# milliLearn-ice40.net
KiCad netlist of a schematic drawn in EAGLE
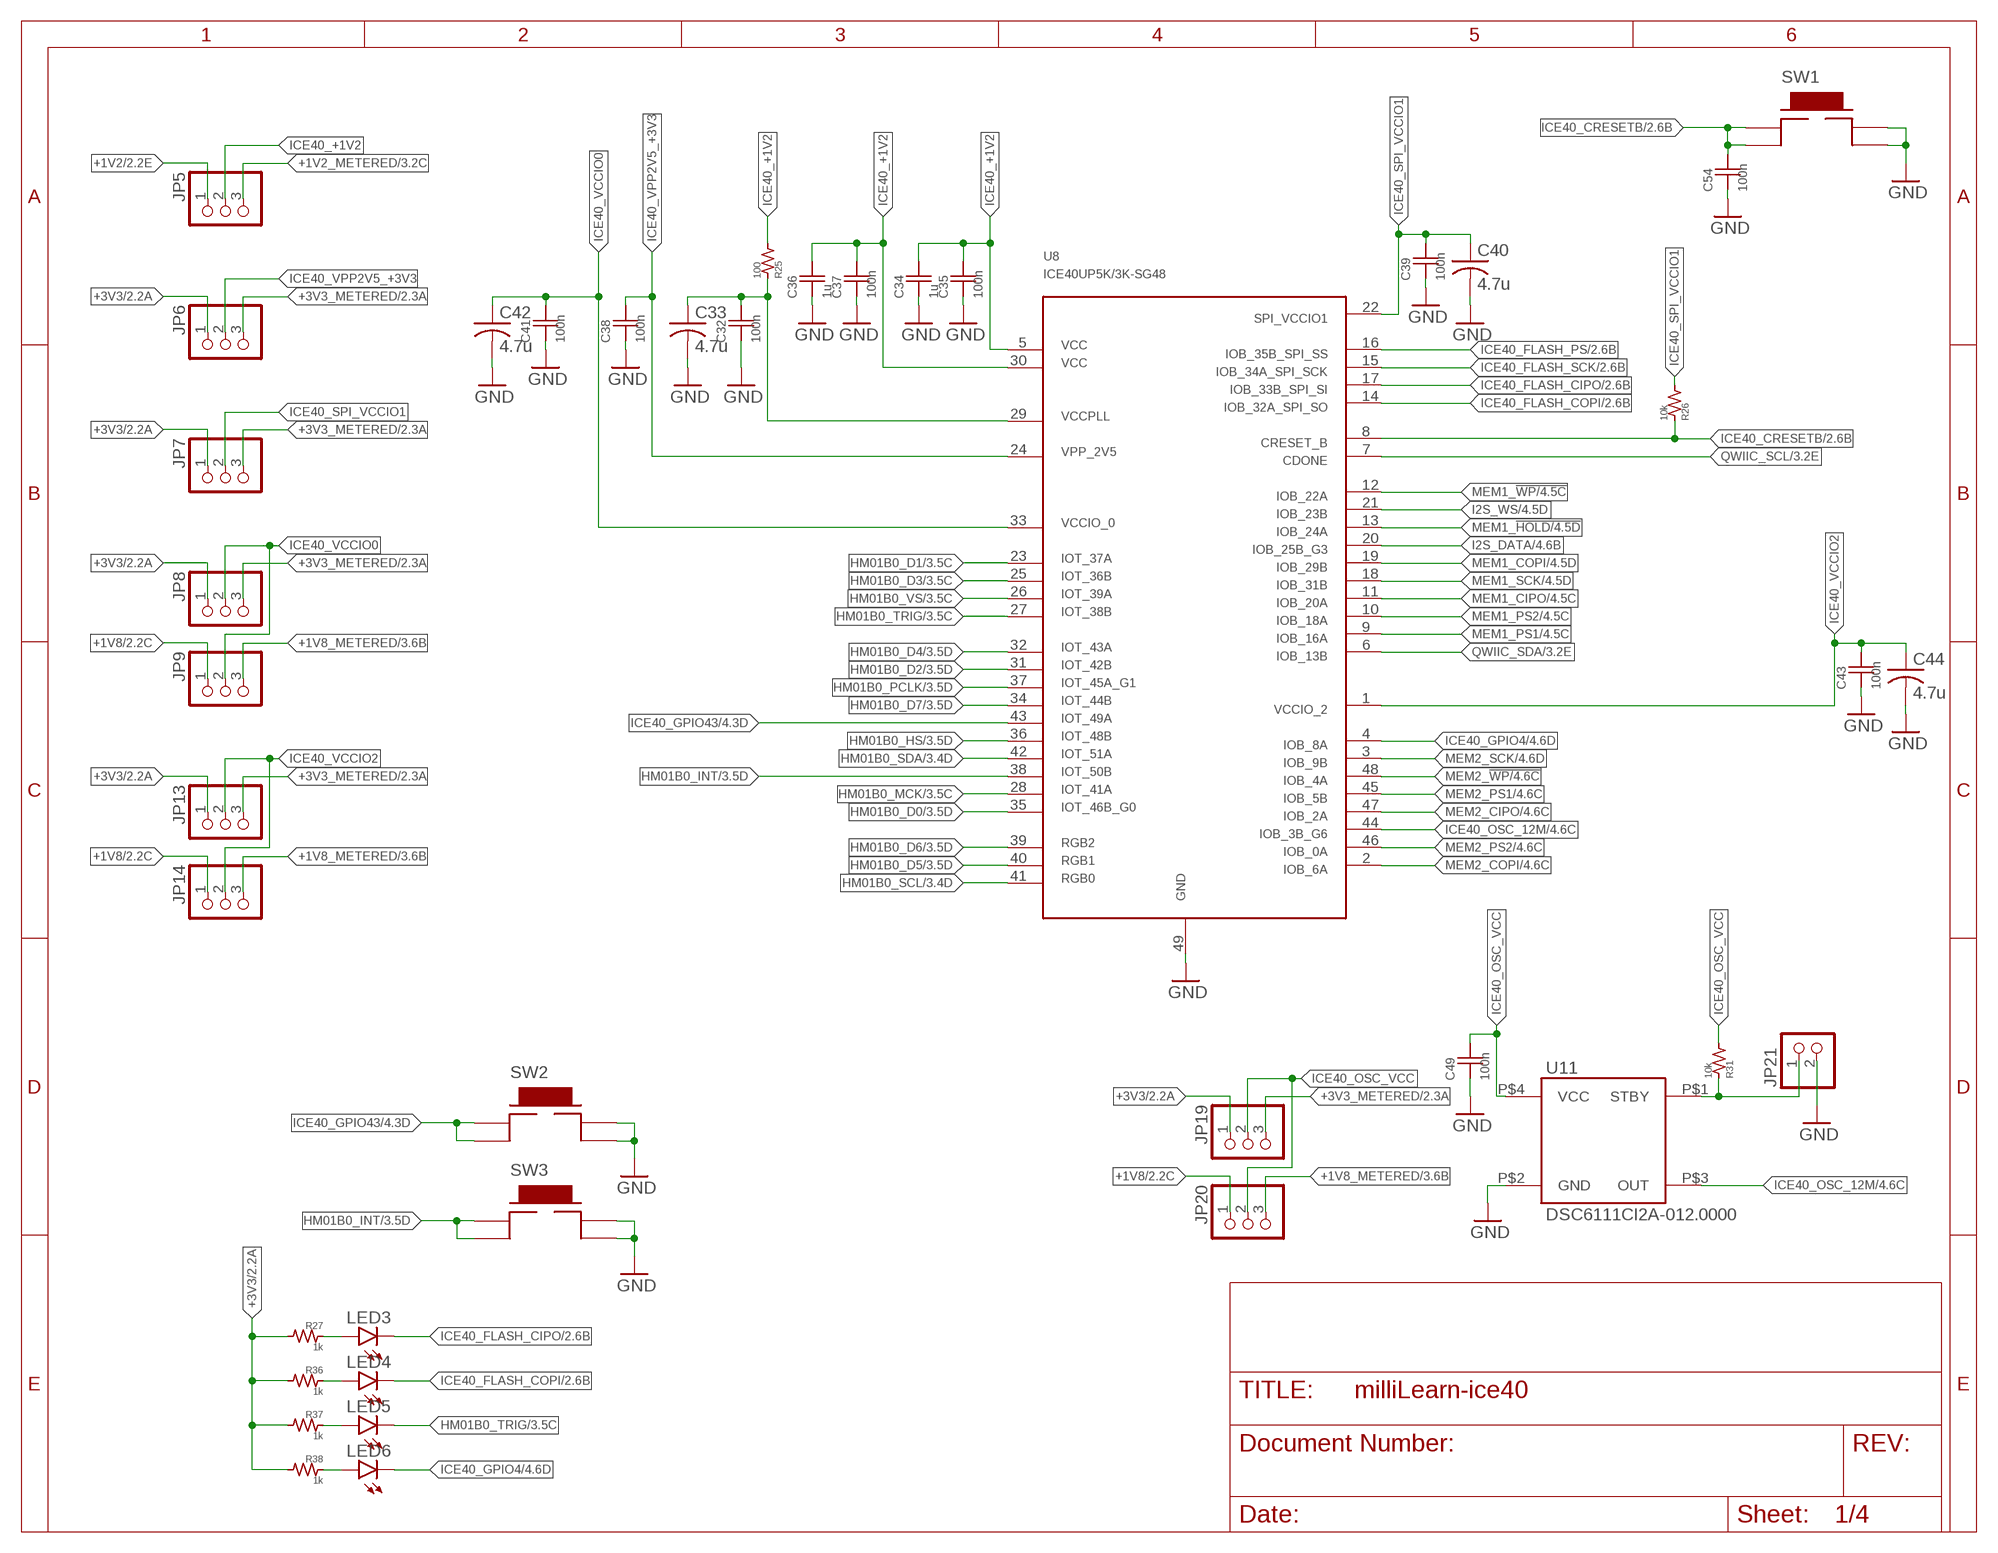
[diagram p0: schematic, sheet 1]
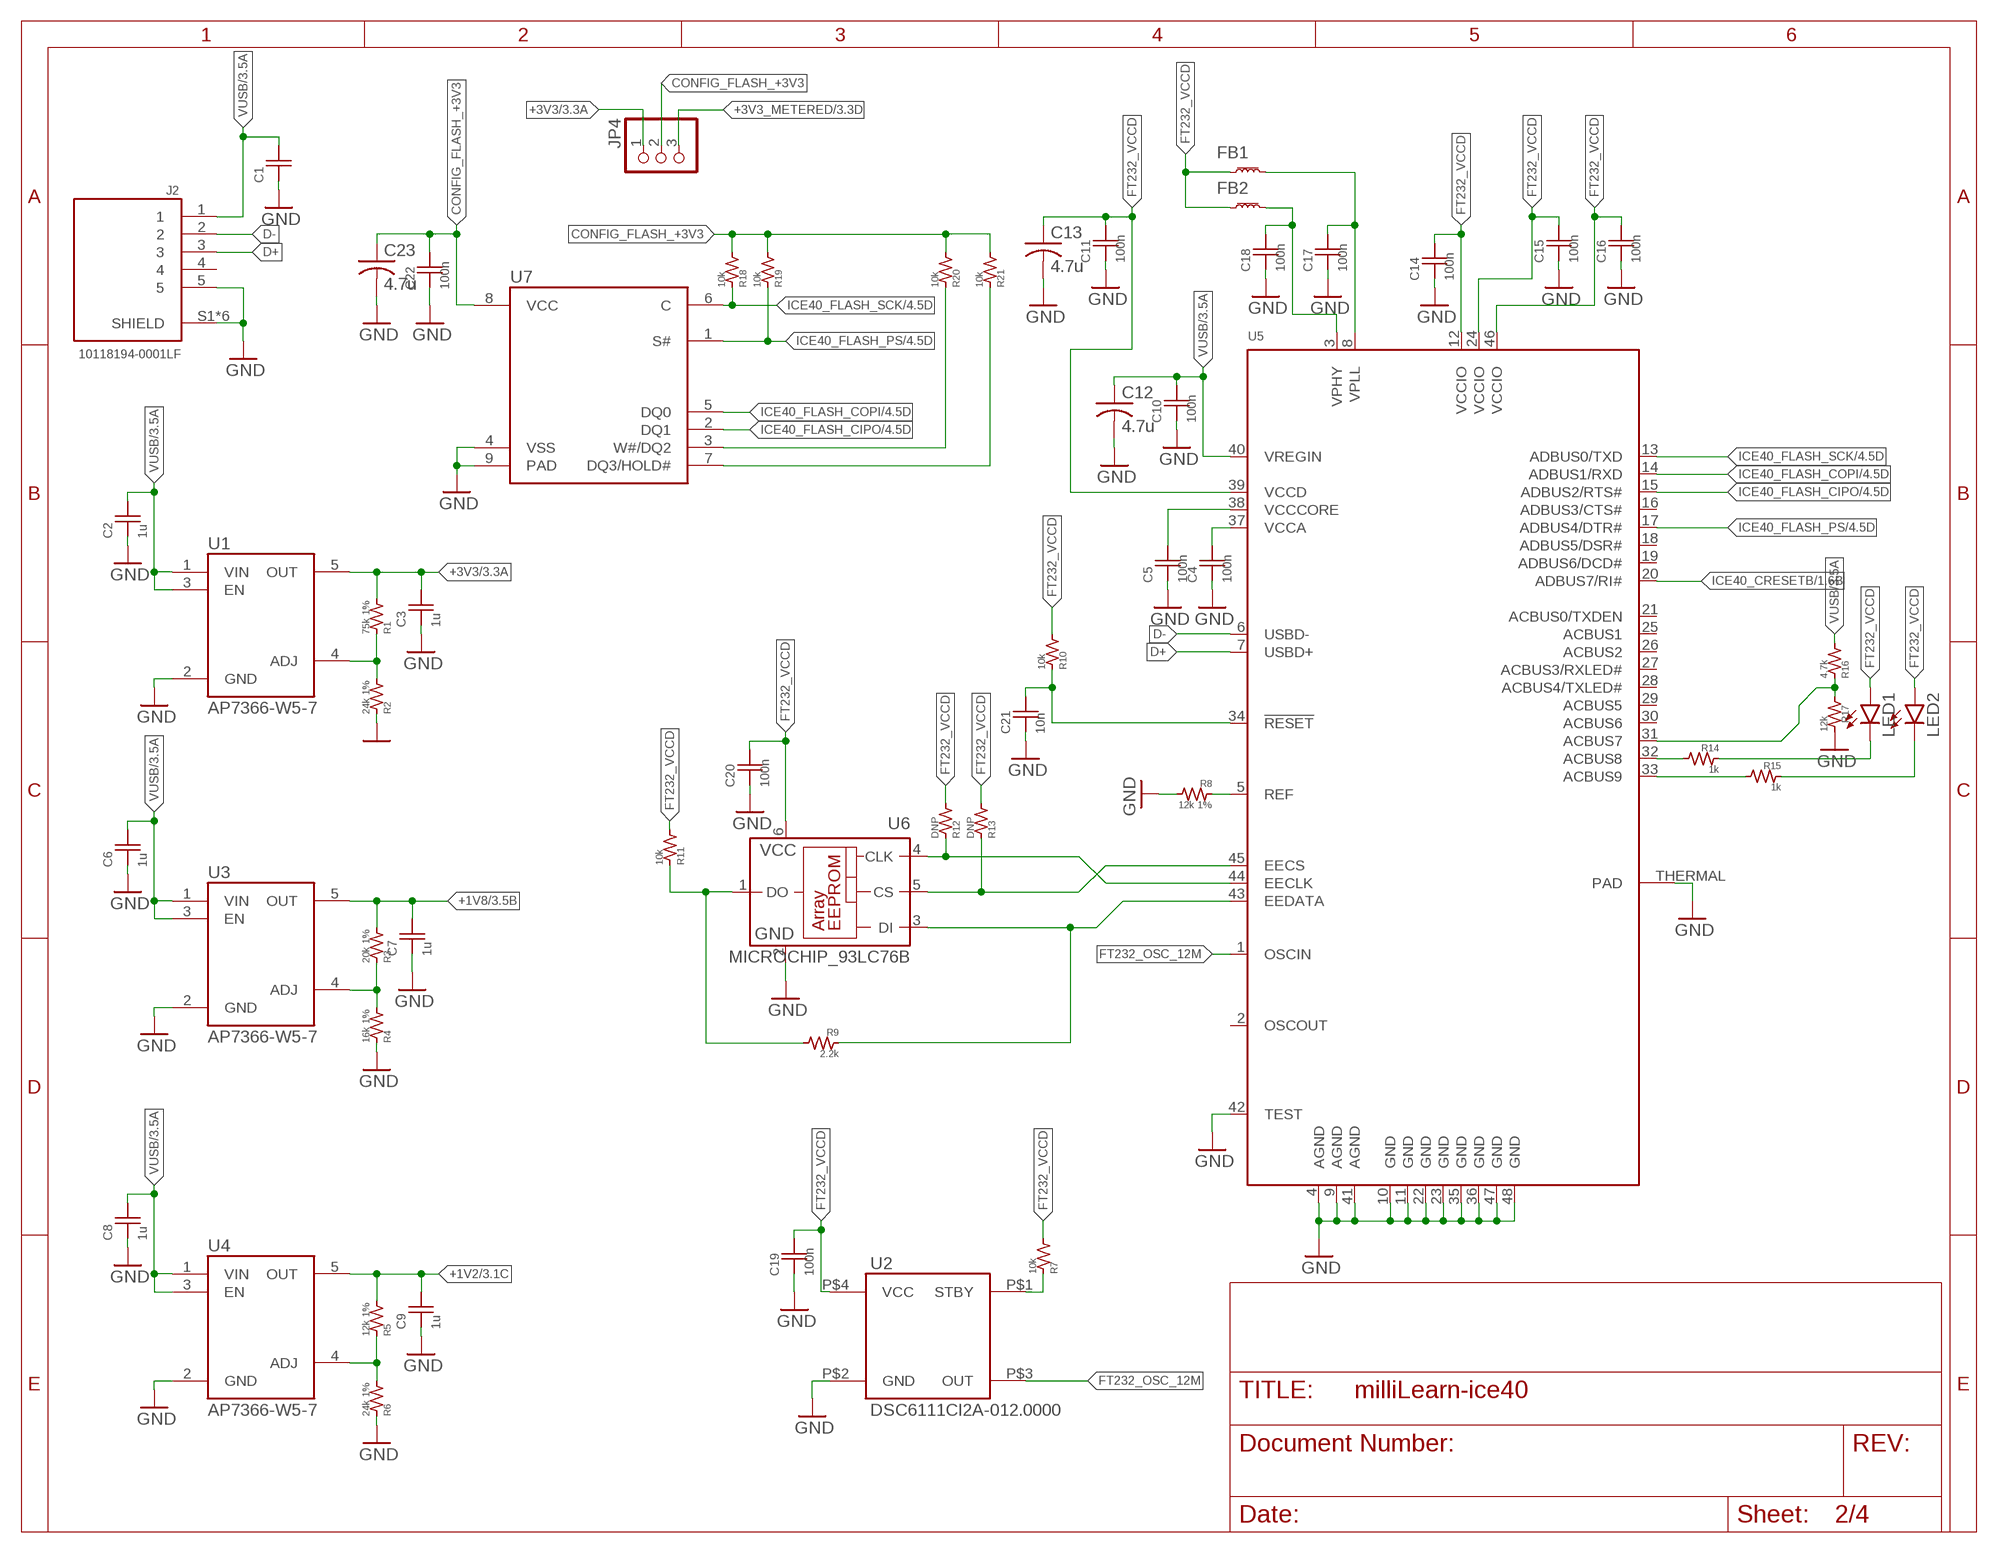
[diagram p1: schematic, sheet 2]
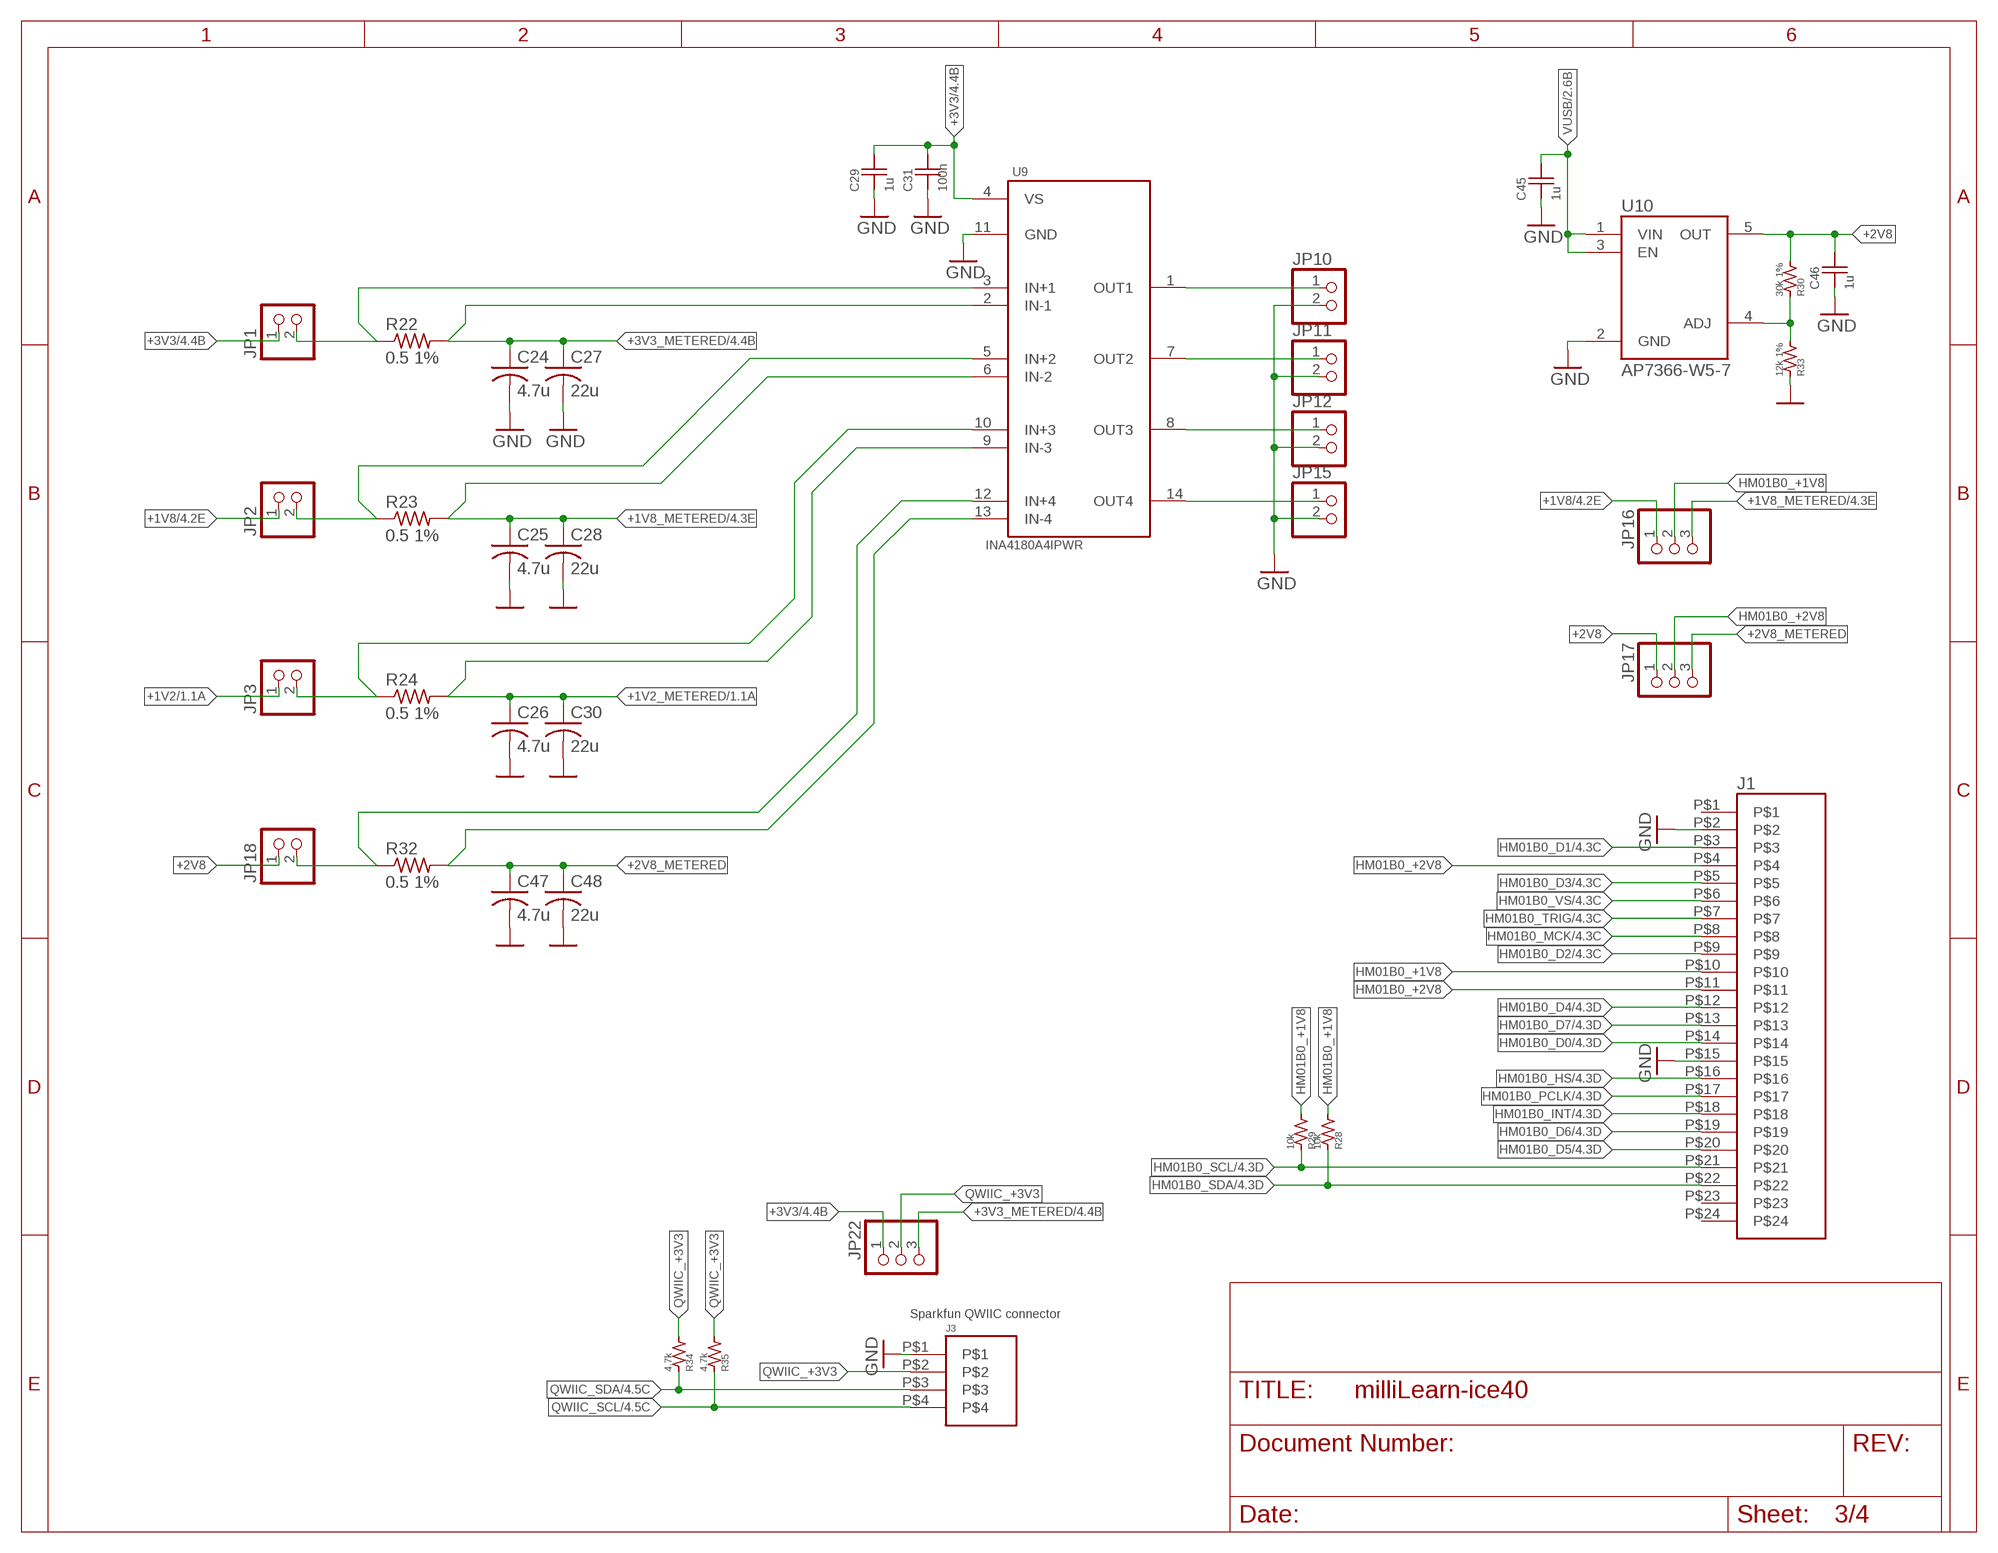
[diagram p2: schematic, sheet 3]
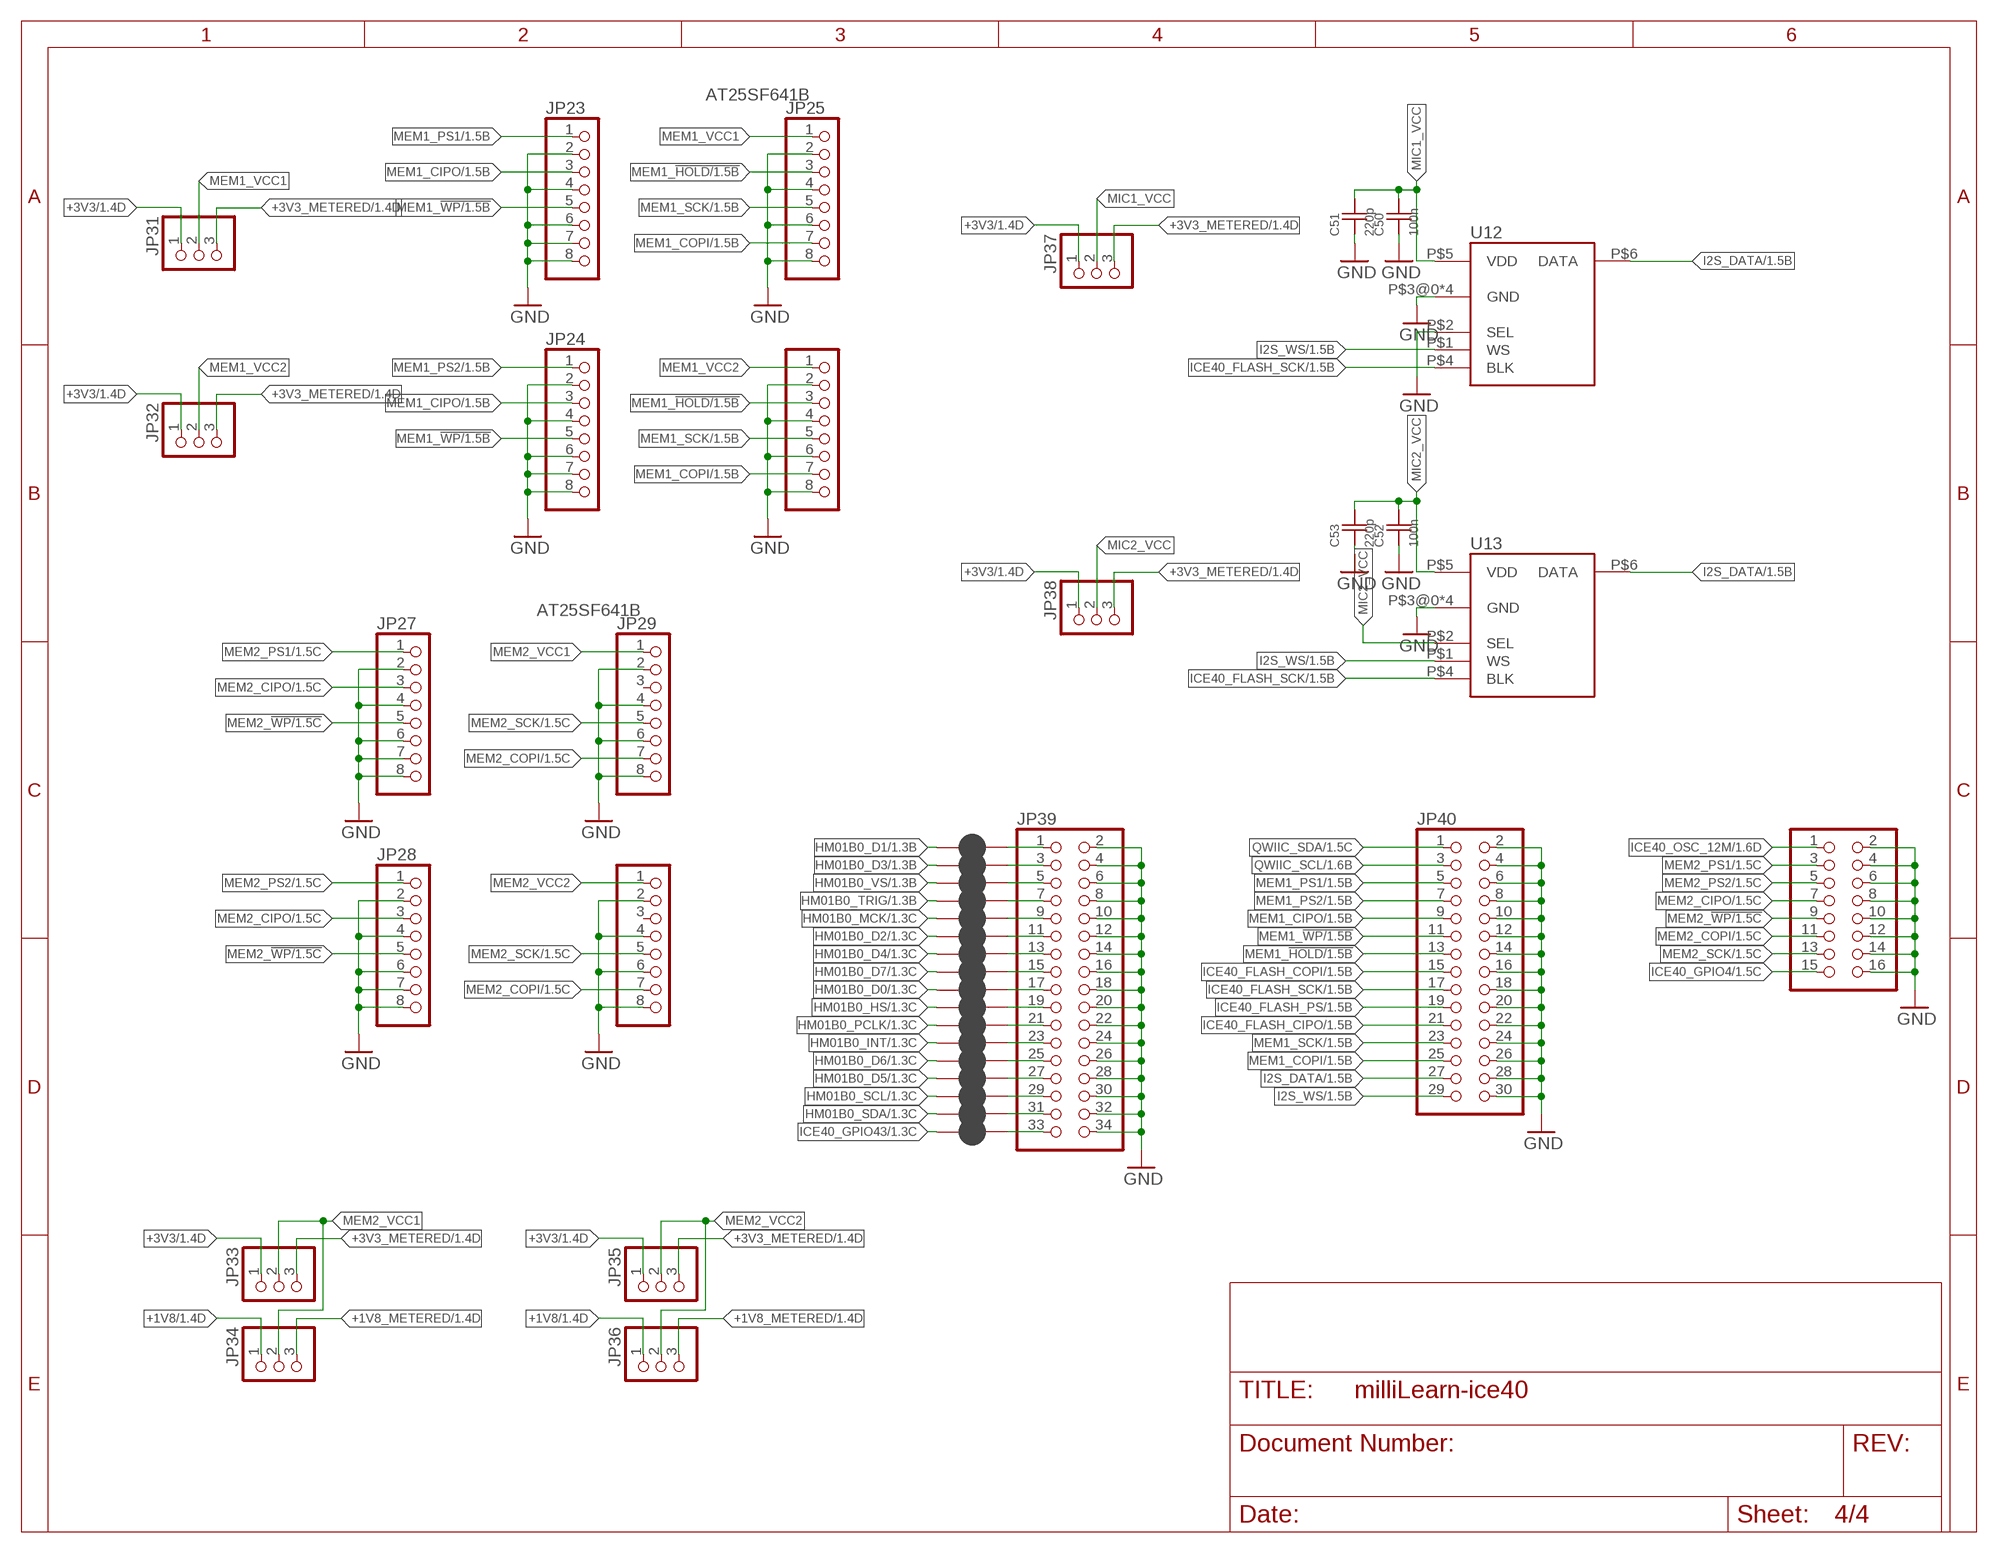
[diagram p3: schematic, sheet 4]

(export (version "E")
  (design (tool "Eeschema 10.0.6"))
  (components
    (comp (ref "C24")
      (value "4.7u")
      (footprint "eagle-import:C0603")
      (fields (field (name "MFR") "SAMSUNG"))
      (libsource (lib "eagle-import") (part "C-USC0603"))
    )
    (comp (ref "C25")
      (value "4.7u")
      (footprint "eagle-import:C0603")
      (fields (field (name "MFR") "SAMSUNG"))
      (libsource (lib "eagle-import") (part "C-USC0603"))
    )
    (comp (ref "C26")
      (value "4.7u")
      (footprint "eagle-import:C0603")
      (fields (field (name "MFR") "SAMSUNG"))
      (libsource (lib "eagle-import") (part "C-USC0603"))
    )
    (comp (ref "C27")
      (value "22u")
      (footprint "eagle-import:C1210")
      (fields (field (name "MFR") "AVX CORPORATION"))
      (libsource (lib "eagle-import") (part "C-USC1210"))
    )
    (comp (ref "C28")
      (value "22u")
      (footprint "eagle-import:C1210")
      (fields (field (name "MFR") "AVX CORPORATION"))
      (libsource (lib "eagle-import") (part "C-USC1210"))
    )
    (comp (ref "C29")
      (value "1u")
      (footprint "eagle-import:C0402_COMPACT")
      (fields (field (name "MFR") "SAMSUNG"))
      (libsource (lib "eagle-import") (part "C0402_COMPACT"))
    )
    (comp (ref "C30")
      (value "22u")
      (footprint "eagle-import:C1210")
      (fields (field (name "MFR") "AVX CORPORATION"))
      (libsource (lib "eagle-import") (part "C-USC1210"))
    )
    (comp (ref "C31")
      (value "100n")
      (footprint "eagle-import:C0402_COMPACT")
      (fields (field (name "MFR") "SAMSUNG"))
      (libsource (lib "eagle-import") (part "C0402_COMPACT"))
    )
    (comp (ref "C45")
      (value "1u")
      (footprint "eagle-import:C0402_COMPACT")
      (fields (field (name "MFR") "SAMSUNG"))
      (libsource (lib "eagle-import") (part "C0402_COMPACT"))
    )
    (comp (ref "C46")
      (value "1u")
      (footprint "eagle-import:C0402_COMPACT")
      (fields (field (name "MFR") "SAMSUNG"))
      (libsource (lib "eagle-import") (part "C0402_COMPACT"))
    )
    (comp (ref "C47")
      (value "4.7u")
      (footprint "eagle-import:C0603")
      (fields (field (name "MFR") "SAMSUNG"))
      (libsource (lib "eagle-import") (part "C-USC0603"))
    )
    (comp (ref "C48")
      (value "22u")
      (footprint "eagle-import:C1210")
      (fields (field (name "MFR") "AVX CORPORATION"))
      (libsource (lib "eagle-import") (part "C-USC1210"))
    )
    (comp (ref "J1")
      (value "SFV24R-2STE1HLF")
      (footprint "eagle-import:SFV24R-2STE1HLF")
      (libsource (lib "eagle-import") (part "SFV24R-2STE1HLF"))
    )
    (comp (ref "J3")
      (value "SM04B-SRSS-TB(LF)(SN)")
      (footprint "eagle-import:SM04B-SRSS-TB(LF)(SN)")
      (libsource (lib "eagle-import") (part "SM04B-SRSS-TB(LF)(SN)"))
    )
    (comp (ref "JP1")
      (value "PINHD-1X2")
      (footprint "eagle-import:1X02")
      (fields (field (name "MFR") "WURTH ELECTRONIK"))
      (libsource (lib "eagle-import") (part "PINHD-1X2"))
    )
    (comp (ref "JP2")
      (value "PINHD-1X2")
      (footprint "eagle-import:1X02")
      (fields (field (name "MFR") "WURTH ELECTRONIK"))
      (libsource (lib "eagle-import") (part "PINHD-1X2"))
    )
    (comp (ref "JP3")
      (value "PINHD-1X2")
      (footprint "eagle-import:1X02")
      (fields (field (name "MFR") "WURTH ELECTRONIK"))
      (libsource (lib "eagle-import") (part "PINHD-1X2"))
    )
    (comp (ref "JP10")
      (value "PINHD-1X2")
      (footprint "eagle-import:1X02")
      (fields (field (name "MFR") "WURTH ELECTRONIK"))
      (libsource (lib "eagle-import") (part "PINHD-1X2"))
    )
    (comp (ref "JP11")
      (value "PINHD-1X2")
      (footprint "eagle-import:1X02")
      (fields (field (name "MFR") "WURTH ELECTRONIK"))
      (libsource (lib "eagle-import") (part "PINHD-1X2"))
    )
    (comp (ref "JP12")
      (value "PINHD-1X2")
      (footprint "eagle-import:1X02")
      (fields (field (name "MFR") "WURTH ELECTRONIK"))
      (libsource (lib "eagle-import") (part "PINHD-1X2"))
    )
    (comp (ref "JP15")
      (value "PINHD-1X2")
      (footprint "eagle-import:1X02")
      (fields (field (name "MFR") "WURTH ELECTRONIK"))
      (libsource (lib "eagle-import") (part "PINHD-1X2"))
    )
    (comp (ref "JP16")
      (value "PINHD-1X3")
      (footprint "eagle-import:1X03")
      (libsource (lib "eagle-import") (part "PINHD-1X3"))
    )
    (comp (ref "JP17")
      (value "PINHD-1X3")
      (footprint "eagle-import:1X03")
      (libsource (lib "eagle-import") (part "PINHD-1X3"))
    )
    (comp (ref "JP18")
      (value "PINHD-1X2")
      (footprint "eagle-import:1X02")
      (fields (field (name "MFR") "WURTH ELECTRONIK"))
      (libsource (lib "eagle-import") (part "PINHD-1X2"))
    )
    (comp (ref "JP22")
      (value "PINHD-1X3")
      (footprint "eagle-import:1X03")
      (libsource (lib "eagle-import") (part "PINHD-1X3"))
    )
    (comp (ref "R22")
      (value "0.5 1%")
      (footprint "eagle-import:R0603")
      (fields (field (name "MFR") "YAGEO"))
      (libsource (lib "eagle-import") (part "R-US_R0603"))
    )
    (comp (ref "R23")
      (value "0.5 1%")
      (footprint "eagle-import:R0603")
      (fields (field (name "MFR") "YAGEO"))
      (libsource (lib "eagle-import") (part "R-US_R0603"))
    )
    (comp (ref "R24")
      (value "0.5 1%")
      (footprint "eagle-import:R0603")
      (fields (field (name "MFR") "YAGEO"))
      (libsource (lib "eagle-import") (part "R-US_R0603"))
    )
    (comp (ref "R28")
      (value "10k")
      (footprint "eagle-import:R0402_COMPACT")
      (fields (field (name "MFR") "PANASONIC"))
      (libsource (lib "eagle-import") (part "R0402_COMPACT"))
    )
    (comp (ref "R29")
      (value "10k")
      (footprint "eagle-import:R0402_COMPACT")
      (fields (field (name "MFR") "PANASONIC"))
      (libsource (lib "eagle-import") (part "R0402_COMPACT"))
    )
    (comp (ref "R30")
      (value "30k 1%")
      (footprint "eagle-import:R0402_COMPACT")
      (fields (field (name "MFR") "PANASONIC"))
      (libsource (lib "eagle-import") (part "R0402_COMPACT"))
    )
    (comp (ref "R32")
      (value "0.5 1%")
      (footprint "eagle-import:R0603")
      (fields (field (name "MFR") "YAGEO"))
      (libsource (lib "eagle-import") (part "R-US_R0603"))
    )
    (comp (ref "R33")
      (value "12k 1%")
      (footprint "eagle-import:R0402_COMPACT")
      (fields (field (name "MFR") "PANASONIC"))
      (libsource (lib "eagle-import") (part "R0402_COMPACT"))
    )
    (comp (ref "R34")
      (value "4.7k")
      (footprint "eagle-import:R0402_COMPACT")
      (fields (field (name "MFR") "PANASONIC"))
      (libsource (lib "eagle-import") (part "R0402_COMPACT"))
    )
    (comp (ref "R35")
      (value "4.7k")
      (footprint "eagle-import:R0402_COMPACT")
      (fields (field (name "MFR") "PANASONIC"))
      (libsource (lib "eagle-import") (part "R0402_COMPACT"))
    )
    (comp (ref "U9")
      (value "INA4180A4IPWR")
      (footprint "eagle-import:INA4180A4IPWR")
      (fields (field (name "MFR") "TI"))
      (libsource (lib "eagle-import") (part "INA4180A4IPWR"))
    )
    (comp (ref "U10")
      (value "AP7366-W5-7")
      (footprint "eagle-import:AP7366-W5-7")
      (fields (field (name "MFR") "Diodes Inc"))
      (libsource (lib "eagle-import") (part "AP7366-W5-7"))
    )
    (comp (ref "C32")
      (value "100n")
      (footprint "eagle-import:C0402_COMPACT")
      (libsource (lib "eagle-import") (part "C0402_COMPACT"))
    )
    (comp (ref "C33")
      (value "4.7u")
      (footprint "eagle-import:C0603")
      (fields (field (name "MFR") "SAMSUNG"))
      (libsource (lib "eagle-import") (part "C-USC0603"))
    )
    (comp (ref "C34")
      (value "1u")
      (footprint "eagle-import:C0402_COMPACT")
      (fields (field (name "MFR") "SAMSUNG"))
      (libsource (lib "eagle-import") (part "C0402_COMPACT"))
    )
    (comp (ref "C35")
      (value "100n")
      (footprint "eagle-import:C0402_COMPACT")
      (fields (field (name "MFR") "SAMSUNG"))
      (libsource (lib "eagle-import") (part "C0402_COMPACT"))
    )
    (comp (ref "C36")
      (value "1u")
      (footprint "eagle-import:C0402_COMPACT")
      (fields (field (name "MFR") "SAMSUNG"))
      (libsource (lib "eagle-import") (part "C0402_COMPACT"))
    )
    (comp (ref "C37")
      (value "100n")
      (footprint "eagle-import:C0402_COMPACT")
      (fields (field (name "MFR") "SAMSUNG"))
      (libsource (lib "eagle-import") (part "C0402_COMPACT"))
    )
    (comp (ref "C38")
      (value "100n")
      (footprint "eagle-import:C0402_COMPACT")
      (libsource (lib "eagle-import") (part "C0402_COMPACT"))
    )
    (comp (ref "C39")
      (value "100n")
      (footprint "eagle-import:C0402_COMPACT")
      (fields (field (name "MFR") "SAMSUNG"))
      (libsource (lib "eagle-import") (part "C0402_COMPACT"))
    )
    (comp (ref "C40")
      (value "4.7u")
      (footprint "eagle-import:C0603")
      (fields (field (name "MFR") "SAMSUNG"))
      (libsource (lib "eagle-import") (part "C-USC0603"))
    )
    (comp (ref "C41")
      (value "100n")
      (footprint "eagle-import:C0402_COMPACT")
      (fields (field (name "MFR") "SAMSUNG"))
      (libsource (lib "eagle-import") (part "C0402_COMPACT"))
    )
    (comp (ref "C42")
      (value "4.7u")
      (footprint "eagle-import:C0603")
      (fields (field (name "MFR") "SAMSUNG"))
      (libsource (lib "eagle-import") (part "C-USC0603"))
    )
    (comp (ref "C43")
      (value "100n")
      (footprint "eagle-import:C0402_COMPACT")
      (fields (field (name "MFR") "SAMSUNG"))
      (libsource (lib "eagle-import") (part "C0402_COMPACT"))
    )
    (comp (ref "C44")
      (value "4.7u")
      (footprint "eagle-import:C0603")
      (fields (field (name "MFR") "SAMSUNG"))
      (libsource (lib "eagle-import") (part "C-USC0603"))
    )
    (comp (ref "C49")
      (value "100n")
      (footprint "eagle-import:C0402_COMPACT")
      (fields (field (name "MFR") "SAMSUNG"))
      (libsource (lib "eagle-import") (part "C0402_COMPACT"))
    )
    (comp (ref "C54")
      (value "100n")
      (footprint "eagle-import:C0402_COMPACT")
      (fields (field (name "MFR") "SAMSUNG"))
      (libsource (lib "eagle-import") (part "C0402_COMPACT"))
    )
    (comp (ref "JP5")
      (value "PINHD-1X3")
      (footprint "eagle-import:1X03")
      (libsource (lib "eagle-import") (part "PINHD-1X3"))
    )
    (comp (ref "JP6")
      (value "PINHD-1X3")
      (footprint "eagle-import:1X03")
      (libsource (lib "eagle-import") (part "PINHD-1X3"))
    )
    (comp (ref "JP7")
      (value "PINHD-1X3")
      (footprint "eagle-import:1X03")
      (libsource (lib "eagle-import") (part "PINHD-1X3"))
    )
    (comp (ref "JP8")
      (value "PINHD-1X3")
      (footprint "eagle-import:1X03")
      (libsource (lib "eagle-import") (part "PINHD-1X3"))
    )
    (comp (ref "JP9")
      (value "PINHD-1X3")
      (footprint "eagle-import:1X03")
      (libsource (lib "eagle-import") (part "PINHD-1X3"))
    )
    (comp (ref "JP13")
      (value "PINHD-1X3")
      (footprint "eagle-import:1X03")
      (libsource (lib "eagle-import") (part "PINHD-1X3"))
    )
    (comp (ref "JP14")
      (value "PINHD-1X3")
      (footprint "eagle-import:1X03")
      (libsource (lib "eagle-import") (part "PINHD-1X3"))
    )
    (comp (ref "JP19")
      (value "PINHD-1X3")
      (footprint "eagle-import:1X03")
      (libsource (lib "eagle-import") (part "PINHD-1X3"))
    )
    (comp (ref "JP20")
      (value "PINHD-1X3")
      (footprint "eagle-import:1X03")
      (libsource (lib "eagle-import") (part "PINHD-1X3"))
    )
    (comp (ref "JP21")
      (value "PINHD-1X2")
      (footprint "eagle-import:1X02")
      (libsource (lib "eagle-import") (part "PINHD-1X2"))
    )
    (comp (ref "LED3")
      (value "LEDCHIPLED_0603")
      (footprint "eagle-import:CHIPLED_0603")
      (fields (field (name "MFR") "LITE-ON"))
      (libsource (lib "eagle-import") (part "LEDCHIPLED_0603"))
    )
    (comp (ref "LED4")
      (value "LEDCHIPLED_0603")
      (footprint "eagle-import:CHIPLED_0603")
      (fields (field (name "MFR") "LITE-ON"))
      (libsource (lib "eagle-import") (part "LEDCHIPLED_0603"))
    )
    (comp (ref "LED5")
      (value "LEDCHIPLED_0603")
      (footprint "eagle-import:CHIPLED_0603")
      (fields (field (name "MFR") "LITE-ON"))
      (libsource (lib "eagle-import") (part "LEDCHIPLED_0603"))
    )
    (comp (ref "LED6")
      (value "LEDCHIPLED_0603")
      (footprint "eagle-import:CHIPLED_0603")
      (fields (field (name "MFR") "LITE-ON"))
      (libsource (lib "eagle-import") (part "LEDCHIPLED_0603"))
    )
    (comp (ref "R25")
      (value "100")
      (footprint "eagle-import:R0402_COMPACT")
      (libsource (lib "eagle-import") (part "R0402_COMPACT"))
    )
    (comp (ref "R26")
      (value "10k")
      (footprint "eagle-import:R0402_COMPACT")
      (fields (field (name "MFR") "PANASONIC"))
      (libsource (lib "eagle-import") (part "R0402_COMPACT"))
    )
    (comp (ref "R27")
      (value "1k")
      (footprint "eagle-import:R0402_COMPACT")
      (fields (field (name "MFR") "PANASONIC"))
      (libsource (lib "eagle-import") (part "R0402_COMPACT"))
    )
    (comp (ref "R31")
      (value "10k")
      (footprint "eagle-import:R0402_COMPACT")
      (fields (field (name "MFR") "PANASONIC"))
      (libsource (lib "eagle-import") (part "R0402_COMPACT"))
    )
    (comp (ref "R36")
      (value "1k")
      (footprint "eagle-import:R0402_COMPACT")
      (fields (field (name "MFR") "PANASONIC"))
      (libsource (lib "eagle-import") (part "R0402_COMPACT"))
    )
    (comp (ref "R37")
      (value "1k")
      (footprint "eagle-import:R0402_COMPACT")
      (fields (field (name "MFR") "PANASONIC"))
      (libsource (lib "eagle-import") (part "R0402_COMPACT"))
    )
    (comp (ref "R38")
      (value "1k")
      (footprint "eagle-import:R0402_COMPACT")
      (fields (field (name "MFR") "PANASONIC"))
      (libsource (lib "eagle-import") (part "R0402_COMPACT"))
    )
    (comp (ref "SW1")
      (value "TE_FSMJSMA")
      (footprint "eagle-import:TE_FSMJSMA")
      (libsource (lib "eagle-import") (part "TE_FSMJSMA"))
    )
    (comp (ref "SW2")
      (value "TE_FSMJSMA")
      (footprint "eagle-import:TE_FSMJSMA")
      (libsource (lib "eagle-import") (part "TE_FSMJSMA"))
    )
    (comp (ref "SW3")
      (value "TE_FSMJSMA")
      (footprint "eagle-import:TE_FSMJSMA")
      (libsource (lib "eagle-import") (part "TE_FSMJSMA"))
    )
    (comp (ref "U8")
      (value "ICE40UP5K/3K-SG48")
      (footprint "eagle-import:ICE40UP5K_3K-SG48")
      (libsource (lib "eagle-import") (part "ICE40UP5K/3K-SG48"))
    )
    (comp (ref "U11")
      (value "DSC6111CI2A-012.0000")
      (footprint "eagle-import:DSC6111CI2A-012.0000")
      (libsource (lib "eagle-import") (part "DSC6111CI2A-012.0000"))
    )
    (comp (ref "C50")
      (value "100n")
      (footprint "eagle-import:C0402_COMPACT")
      (fields (field (name "MFR") "SAMSUNG"))
      (libsource (lib "eagle-import") (part "C0402_COMPACT"))
    )
    (comp (ref "C51")
      (value "220p")
      (footprint "eagle-import:C0402_COMPACT")
      (fields (field (name "MFR") "SAMSUNG"))
      (libsource (lib "eagle-import") (part "C0402_COMPACT"))
    )
    (comp (ref "C52")
      (value "100n")
      (footprint "eagle-import:C0402_COMPACT")
      (fields (field (name "MFR") "SAMSUNG"))
      (libsource (lib "eagle-import") (part "C0402_COMPACT"))
    )
    (comp (ref "C53")
      (value "220p")
      (footprint "eagle-import:C0402_COMPACT")
      (fields (field (name "MFR") "SAMSUNG"))
      (libsource (lib "eagle-import") (part "C0402_COMPACT"))
    )
    (comp (ref "JP23")
      (value "PINHD-1X8")
      (footprint "eagle-import:1X08")
      (libsource (lib "eagle-import") (part "PINHD-1X8"))
    )
    (comp (ref "JP24")
      (value "PINHD-1X8")
      (footprint "eagle-import:1X08")
      (libsource (lib "eagle-import") (part "PINHD-1X8"))
    )
    (comp (ref "JP25")
      (value "PINHD-1X8")
      (footprint "eagle-import:1X08")
      (libsource (lib "eagle-import") (part "PINHD-1X8"))
    )
    (comp (ref "JP26")
      (value "PINHD-1X8")
      (footprint "eagle-import:1X08")
      (libsource (lib "eagle-import") (part "PINHD-1X8"))
    )
    (comp (ref "JP27")
      (value "PINHD-1X8")
      (footprint "eagle-import:1X08")
      (libsource (lib "eagle-import") (part "PINHD-1X8"))
    )
    (comp (ref "JP28")
      (value "PINHD-1X8")
      (footprint "eagle-import:1X08")
      (libsource (lib "eagle-import") (part "PINHD-1X8"))
    )
    (comp (ref "JP29")
      (value "PINHD-1X8")
      (footprint "eagle-import:1X08")
      (libsource (lib "eagle-import") (part "PINHD-1X8"))
    )
    (comp (ref "JP30")
      (value "PINHD-1X8")
      (footprint "eagle-import:1X08")
      (libsource (lib "eagle-import") (part "PINHD-1X8"))
    )
    (comp (ref "JP31")
      (value "PINHD-1X3")
      (footprint "eagle-import:1X03")
      (libsource (lib "eagle-import") (part "PINHD-1X3"))
    )
    (comp (ref "JP32")
      (value "PINHD-1X3")
      (footprint "eagle-import:1X03")
      (libsource (lib "eagle-import") (part "PINHD-1X3"))
    )
    (comp (ref "JP33")
      (value "PINHD-1X3")
      (footprint "eagle-import:1X03")
      (libsource (lib "eagle-import") (part "PINHD-1X3"))
    )
    (comp (ref "JP34")
      (value "PINHD-1X3")
      (footprint "eagle-import:1X03")
      (libsource (lib "eagle-import") (part "PINHD-1X3"))
    )
    (comp (ref "JP35")
      (value "PINHD-1X3")
      (footprint "eagle-import:1X03")
      (libsource (lib "eagle-import") (part "PINHD-1X3"))
    )
    (comp (ref "JP36")
      (value "PINHD-1X3")
      (footprint "eagle-import:1X03")
      (libsource (lib "eagle-import") (part "PINHD-1X3"))
    )
    (comp (ref "JP37")
      (value "PINHD-1X3")
      (footprint "eagle-import:1X03")
      (libsource (lib "eagle-import") (part "PINHD-1X3"))
    )
    (comp (ref "JP38")
      (value "PINHD-1X3")
      (footprint "eagle-import:1X03")
      (libsource (lib "eagle-import") (part "PINHD-1X3"))
    )
    (comp (ref "JP39")
      (value "PINHD-2X17")
      (footprint "eagle-import:2X17")
      (libsource (lib "eagle-import") (part "PINHD-2X17"))
    )
    (comp (ref "JP40")
      (value "PINHD-2X15")
      (footprint "eagle-import:2X15")
      (libsource (lib "eagle-import") (part "PINHD-2X15"))
    )
    (comp (ref "JP41")
      (value "PINHD-2X8")
      (footprint "eagle-import:2X08")
      (libsource (lib "eagle-import") (part "PINHD-2X8"))
    )
    (comp (ref "SJ1")
      (value "JUMPER-SMT_2_NC_PASTE_NO-SILK")
      (footprint "eagle-import:SMT-JUMPER_2_NC_PASTE_NO-SILK")
      (libsource (lib "eagle-import") (part "JUMPER-SMT_2_NC_PASTE_NO-SILK"))
    )
    (comp (ref "SJ2")
      (value "JUMPER-SMT_2_NC_PASTE_NO-SILK")
      (footprint "eagle-import:SMT-JUMPER_2_NC_PASTE_NO-SILK")
      (libsource (lib "eagle-import") (part "JUMPER-SMT_2_NC_PASTE_NO-SILK"))
    )
    (comp (ref "SJ3")
      (value "JUMPER-SMT_2_NC_PASTE_NO-SILK")
      (footprint "eagle-import:SMT-JUMPER_2_NC_PASTE_NO-SILK")
      (libsource (lib "eagle-import") (part "JUMPER-SMT_2_NC_PASTE_NO-SILK"))
    )
    (comp (ref "SJ4")
      (value "JUMPER-SMT_2_NC_PASTE_NO-SILK")
      (footprint "eagle-import:SMT-JUMPER_2_NC_PASTE_NO-SILK")
      (libsource (lib "eagle-import") (part "JUMPER-SMT_2_NC_PASTE_NO-SILK"))
    )
    (comp (ref "SJ5")
      (value "JUMPER-SMT_2_NC_PASTE_NO-SILK")
      (footprint "eagle-import:SMT-JUMPER_2_NC_PASTE_NO-SILK")
      (libsource (lib "eagle-import") (part "JUMPER-SMT_2_NC_PASTE_NO-SILK"))
    )
    (comp (ref "SJ6")
      (value "JUMPER-SMT_2_NC_PASTE_NO-SILK")
      (footprint "eagle-import:SMT-JUMPER_2_NC_PASTE_NO-SILK")
      (libsource (lib "eagle-import") (part "JUMPER-SMT_2_NC_PASTE_NO-SILK"))
    )
    (comp (ref "SJ7")
      (value "JUMPER-SMT_2_NC_PASTE_NO-SILK")
      (footprint "eagle-import:SMT-JUMPER_2_NC_PASTE_NO-SILK")
      (libsource (lib "eagle-import") (part "JUMPER-SMT_2_NC_PASTE_NO-SILK"))
    )
    (comp (ref "SJ8")
      (value "JUMPER-SMT_2_NC_PASTE_NO-SILK")
      (footprint "eagle-import:SMT-JUMPER_2_NC_PASTE_NO-SILK")
      (libsource (lib "eagle-import") (part "JUMPER-SMT_2_NC_PASTE_NO-SILK"))
    )
    (comp (ref "SJ9")
      (value "JUMPER-SMT_2_NC_PASTE_NO-SILK")
      (footprint "eagle-import:SMT-JUMPER_2_NC_PASTE_NO-SILK")
      (libsource (lib "eagle-import") (part "JUMPER-SMT_2_NC_PASTE_NO-SILK"))
    )
    (comp (ref "SJ10")
      (value "JUMPER-SMT_2_NC_PASTE_NO-SILK")
      (footprint "eagle-import:SMT-JUMPER_2_NC_PASTE_NO-SILK")
      (libsource (lib "eagle-import") (part "JUMPER-SMT_2_NC_PASTE_NO-SILK"))
    )
    (comp (ref "SJ11")
      (value "JUMPER-SMT_2_NC_PASTE_NO-SILK")
      (footprint "eagle-import:SMT-JUMPER_2_NC_PASTE_NO-SILK")
      (libsource (lib "eagle-import") (part "JUMPER-SMT_2_NC_PASTE_NO-SILK"))
    )
    (comp (ref "SJ12")
      (value "JUMPER-SMT_2_NC_PASTE_NO-SILK")
      (footprint "eagle-import:SMT-JUMPER_2_NC_PASTE_NO-SILK")
      (libsource (lib "eagle-import") (part "JUMPER-SMT_2_NC_PASTE_NO-SILK"))
    )
    (comp (ref "SJ13")
      (value "JUMPER-SMT_2_NC_PASTE_NO-SILK")
      (footprint "eagle-import:SMT-JUMPER_2_NC_PASTE_NO-SILK")
      (libsource (lib "eagle-import") (part "JUMPER-SMT_2_NC_PASTE_NO-SILK"))
    )
    (comp (ref "SJ14")
      (value "JUMPER-SMT_2_NC_PASTE_NO-SILK")
      (footprint "eagle-import:SMT-JUMPER_2_NC_PASTE_NO-SILK")
      (libsource (lib "eagle-import") (part "JUMPER-SMT_2_NC_PASTE_NO-SILK"))
    )
    (comp (ref "SJ15")
      (value "JUMPER-SMT_2_NC_PASTE_NO-SILK")
      (footprint "eagle-import:SMT-JUMPER_2_NC_PASTE_NO-SILK")
      (libsource (lib "eagle-import") (part "JUMPER-SMT_2_NC_PASTE_NO-SILK"))
    )
    (comp (ref "SJ16")
      (value "JUMPER-SMT_2_NC_PASTE_NO-SILK")
      (footprint "eagle-import:SMT-JUMPER_2_NC_PASTE_NO-SILK")
      (libsource (lib "eagle-import") (part "JUMPER-SMT_2_NC_PASTE_NO-SILK"))
    )
    (comp (ref "SJ17")
      (value "JUMPER-SMT_2_NC_PASTE_NO-SILK")
      (footprint "eagle-import:SMT-JUMPER_2_NC_PASTE_NO-SILK")
      (libsource (lib "eagle-import") (part "JUMPER-SMT_2_NC_PASTE_NO-SILK"))
    )
    (comp (ref "U12")
      (value "SPH0645LM4H-B")
      (footprint "eagle-import:SPH0645LM4H-B")
      (fields (field (name "MFR") "KNOWLES"))
      (libsource (lib "eagle-import") (part "SPH0645LM4H-B"))
    )
    (comp (ref "U13")
      (value "SPH0645LM4H-B")
      (footprint "eagle-import:SPH0645LM4H-B")
      (fields (field (name "MFR") "KNOWLES"))
      (libsource (lib "eagle-import") (part "SPH0645LM4H-B"))
    )
    (comp (ref "C1")
      (value "C0402_COMPACT")
      (footprint "eagle-import:C0402_COMPACT")
      (libsource (lib "eagle-import") (part "C0402_COMPACT"))
    )
    (comp (ref "C2")
      (value "1u")
      (footprint "eagle-import:C0402_COMPACT")
      (fields (field (name "MFR") "SAMSUNG"))
      (libsource (lib "eagle-import") (part "C0402_COMPACT"))
    )
    (comp (ref "C3")
      (value "1u")
      (footprint "eagle-import:C0402_COMPACT")
      (fields (field (name "MFR") "SAMSUNG"))
      (libsource (lib "eagle-import") (part "C0402_COMPACT"))
    )
    (comp (ref "C4")
      (value "100n")
      (footprint "eagle-import:C0402_COMPACT")
      (fields (field (name "MFR") "SAMSUNG"))
      (libsource (lib "eagle-import") (part "C0402_COMPACT"))
    )
    (comp (ref "C5")
      (value "100n")
      (footprint "eagle-import:C0402_COMPACT")
      (fields (field (name "MFR") "SAMSUNG"))
      (libsource (lib "eagle-import") (part "C0402_COMPACT"))
    )
    (comp (ref "C6")
      (value "1u")
      (footprint "eagle-import:C0402_COMPACT")
      (fields (field (name "MFR") "SAMSUNG"))
      (libsource (lib "eagle-import") (part "C0402_COMPACT"))
    )
    (comp (ref "C7")
      (value "1u")
      (footprint "eagle-import:C0402_COMPACT")
      (fields (field (name "MFR") "SAMSUNG"))
      (libsource (lib "eagle-import") (part "C0402_COMPACT"))
    )
    (comp (ref "C8")
      (value "1u")
      (footprint "eagle-import:C0402_COMPACT")
      (fields (field (name "MFR") "SAMSUNG"))
      (libsource (lib "eagle-import") (part "C0402_COMPACT"))
    )
    (comp (ref "C9")
      (value "1u")
      (footprint "eagle-import:C0402_COMPACT")
      (fields (field (name "MFR") "SAMSUNG"))
      (libsource (lib "eagle-import") (part "C0402_COMPACT"))
    )
    (comp (ref "C10")
      (value "100n")
      (footprint "eagle-import:C0402_COMPACT")
      (fields (field (name "MFR") "SAMSUNG"))
      (libsource (lib "eagle-import") (part "C0402_COMPACT"))
    )
    (comp (ref "C11")
      (value "100n")
      (footprint "eagle-import:C0402_COMPACT")
      (fields (field (name "MFR") "SAMSUNG"))
      (libsource (lib "eagle-import") (part "C0402_COMPACT"))
    )
    (comp (ref "C12")
      (value "4.7u")
      (footprint "eagle-import:C0603")
      (fields (field (name "MFR") "SAMSUNG"))
      (libsource (lib "eagle-import") (part "C-USC0603"))
    )
    (comp (ref "C13")
      (value "4.7u")
      (footprint "eagle-import:C0603")
      (fields (field (name "MFR") "SAMSUNG"))
      (libsource (lib "eagle-import") (part "C-USC0603"))
    )
    (comp (ref "C14")
      (value "100n")
      (footprint "eagle-import:C0402_COMPACT")
      (fields (field (name "MFR") "SAMSUNG"))
      (libsource (lib "eagle-import") (part "C0402_COMPACT"))
    )
    (comp (ref "C15")
      (value "100n")
      (footprint "eagle-import:C0402_COMPACT")
      (fields (field (name "MFR") "SAMSUNG"))
      (libsource (lib "eagle-import") (part "C0402_COMPACT"))
    )
    (comp (ref "C16")
      (value "100n")
      (footprint "eagle-import:C0402_COMPACT")
      (fields (field (name "MFR") "SAMSUNG"))
      (libsource (lib "eagle-import") (part "C0402_COMPACT"))
    )
    (comp (ref "C17")
      (value "100n")
      (footprint "eagle-import:C0402_COMPACT")
      (fields (field (name "MFR") "SAMSUNG"))
      (libsource (lib "eagle-import") (part "C0402_COMPACT"))
    )
    (comp (ref "C18")
      (value "100n")
      (footprint "eagle-import:C0402_COMPACT")
      (fields (field (name "MFR") "SAMSUNG"))
      (libsource (lib "eagle-import") (part "C0402_COMPACT"))
    )
    (comp (ref "C19")
      (value "100n")
      (footprint "eagle-import:C0402_COMPACT")
      (fields (field (name "MFR") "SAMSUNG"))
      (libsource (lib "eagle-import") (part "C0402_COMPACT"))
    )
    (comp (ref "C20")
      (value "100n")
      (footprint "eagle-import:C0402_COMPACT")
      (fields (field (name "MFR") "SAMSUNG"))
      (libsource (lib "eagle-import") (part "C0402_COMPACT"))
    )
    (comp (ref "C21")
      (value "10n")
      (footprint "eagle-import:C0402_COMPACT")
      (fields (field (name "MFR") "SAMSUNG"))
      (libsource (lib "eagle-import") (part "C0402_COMPACT"))
    )
    (comp (ref "C22")
      (value "100n")
      (footprint "eagle-import:C0402_COMPACT")
      (fields (field (name "MFR") "SAMSUNG"))
      (libsource (lib "eagle-import") (part "C0402_COMPACT"))
    )
    (comp (ref "C23")
      (value "4.7u")
      (footprint "eagle-import:C0603")
      (fields (field (name "MFR") "SAMSUNG"))
      (libsource (lib "eagle-import") (part "C-USC0603"))
    )
    (comp (ref "FB1")
      (value "BLM18KG601SN1D")
      (footprint "eagle-import:BLM18KG601SN1D")
      (fields (field (name "MFR") "MURATA"))
      (libsource (lib "eagle-import") (part "BLM18KG601SN1D"))
    )
    (comp (ref "FB2")
      (value "BLM18KG601SN1D")
      (footprint "eagle-import:BLM18KG601SN1D")
      (fields (field (name "MFR") "MURATA"))
      (libsource (lib "eagle-import") (part "BLM18KG601SN1D"))
    )
    (comp (ref "J2")
      (value "10118194-0001LF")
      (footprint "eagle-import:AMPHENOL_10118194-0001LF")
      (fields (field (name "MF") "Amphenol ICC"))
      (libsource (lib "eagle-import") (part "10118194-0001LF"))
    )
    (comp (ref "JP4")
      (value "PINHD-1X3")
      (footprint "eagle-import:1X03")
      (libsource (lib "eagle-import") (part "PINHD-1X3"))
    )
    (comp (ref "LED1")
      (value "LEDCHIPLED_0603")
      (footprint "eagle-import:CHIPLED_0603")
      (fields (field (name "MFR") "LITE-ON"))
      (libsource (lib "eagle-import") (part "LEDCHIPLED_0603"))
    )
    (comp (ref "LED2")
      (value "LEDCHIPLED_0603")
      (footprint "eagle-import:CHIPLED_0603")
      (fields (field (name "MFR") "LITE-ON"))
      (libsource (lib "eagle-import") (part "LEDCHIPLED_0603"))
    )
    (comp (ref "R1")
      (value "75k 1%")
      (footprint "eagle-import:R0402_COMPACT")
      (fields (field (name "MFR") "PANASONIC"))
      (libsource (lib "eagle-import") (part "R0402_COMPACT"))
    )
    (comp (ref "R2")
      (value "24k 1%")
      (footprint "eagle-import:R0402_COMPACT")
      (fields (field (name "MFR") "PANASONIC"))
      (libsource (lib "eagle-import") (part "R0402_COMPACT"))
    )
    (comp (ref "R3")
      (value "20k 1%")
      (footprint "eagle-import:R0402_COMPACT")
      (fields (field (name "MFR") "PANASONIC"))
      (libsource (lib "eagle-import") (part "R0402_COMPACT"))
    )
    (comp (ref "R4")
      (value "16k 1%")
      (footprint "eagle-import:R0402_COMPACT")
      (fields (field (name "MFR") "PANASONIC"))
      (libsource (lib "eagle-import") (part "R0402_COMPACT"))
    )
    (comp (ref "R5")
      (value "12k 1%")
      (footprint "eagle-import:R0402_COMPACT")
      (fields (field (name "MFR") "PANASONIC"))
      (libsource (lib "eagle-import") (part "R0402_COMPACT"))
    )
    (comp (ref "R6")
      (value "24k 1%")
      (footprint "eagle-import:R0402_COMPACT")
      (fields (field (name "MFR") "PANASONIC"))
      (libsource (lib "eagle-import") (part "R0402_COMPACT"))
    )
    (comp (ref "R7")
      (value "10k")
      (footprint "eagle-import:R0402_COMPACT")
      (fields (field (name "MFR") "PANASONIC"))
      (libsource (lib "eagle-import") (part "R0402_COMPACT"))
    )
    (comp (ref "R8")
      (value "12k 1%")
      (footprint "eagle-import:R0402_COMPACT")
      (fields (field (name "MFR") "PANASONIC"))
      (libsource (lib "eagle-import") (part "R0402_COMPACT"))
    )
    (comp (ref "R9")
      (value "2.2k")
      (footprint "eagle-import:R0402_COMPACT")
      (fields (field (name "MFR") "PANASONIC"))
      (libsource (lib "eagle-import") (part "R0402_COMPACT"))
    )
    (comp (ref "R10")
      (value "10k")
      (footprint "eagle-import:R0402_COMPACT")
      (fields (field (name "MFR") "PANASONIC"))
      (libsource (lib "eagle-import") (part "R0402_COMPACT"))
    )
    (comp (ref "R11")
      (value "10k")
      (footprint "eagle-import:R0402_COMPACT")
      (fields (field (name "MFR") "PANASONIC"))
      (libsource (lib "eagle-import") (part "R0402_COMPACT"))
    )
    (comp (ref "R12")
      (value "DNP")
      (footprint "eagle-import:R0402_COMPACT")
      (fields (field (name "MFR") "PANASONIC"))
      (libsource (lib "eagle-import") (part "R0402_COMPACT"))
    )
    (comp (ref "R13")
      (value "DNP")
      (footprint "eagle-import:R0402_COMPACT")
      (fields (field (name "MFR") "PANASONIC"))
      (libsource (lib "eagle-import") (part "R0402_COMPACT"))
    )
    (comp (ref "R14")
      (value "1k")
      (footprint "eagle-import:R0402_COMPACT")
      (fields (field (name "MFR") "PANASONIC"))
      (libsource (lib "eagle-import") (part "R0402_COMPACT"))
    )
    (comp (ref "R15")
      (value "1k")
      (footprint "eagle-import:R0402_COMPACT")
      (fields (field (name "MFR") "PANASONIC"))
      (libsource (lib "eagle-import") (part "R0402_COMPACT"))
    )
    (comp (ref "R16")
      (value "4.7k")
      (footprint "eagle-import:R0402_COMPACT")
      (fields (field (name "MFR") "PANASONIC"))
      (libsource (lib "eagle-import") (part "R0402_COMPACT"))
    )
    (comp (ref "R17")
      (value "12k")
      (footprint "eagle-import:R0402_COMPACT")
      (fields (field (name "MFR") "PANASONIC"))
      (libsource (lib "eagle-import") (part "R0402_COMPACT"))
    )
    (comp (ref "R18")
      (value "10k")
      (footprint "eagle-import:R0402_COMPACT")
      (fields (field (name "MFR") "PANASONIC"))
      (libsource (lib "eagle-import") (part "R0402_COMPACT"))
    )
    (comp (ref "R19")
      (value "10k")
      (footprint "eagle-import:R0402_COMPACT")
      (fields (field (name "MFR") "PANASONIC"))
      (libsource (lib "eagle-import") (part "R0402_COMPACT"))
    )
    (comp (ref "R20")
      (value "10k")
      (footprint "eagle-import:R0402_COMPACT")
      (fields (field (name "MFR") "PANASONIC"))
      (libsource (lib "eagle-import") (part "R0402_COMPACT"))
    )
    (comp (ref "R21")
      (value "10k")
      (footprint "eagle-import:R0402_COMPACT")
      (fields (field (name "MFR") "PANASONIC"))
      (libsource (lib "eagle-import") (part "R0402_COMPACT"))
    )
    (comp (ref "U1")
      (value "AP7366-W5-7")
      (footprint "eagle-import:AP7366-W5-7")
      (fields (field (name "MFR") "Diodes Inc"))
      (libsource (lib "eagle-import") (part "AP7366-W5-7"))
    )
    (comp (ref "U2")
      (value "DSC6111CI2A-012.0000")
      (footprint "eagle-import:DSC6111CI2A-012.0000")
      (libsource (lib "eagle-import") (part "DSC6111CI2A-012.0000"))
    )
    (comp (ref "U3")
      (value "AP7366-W5-7")
      (footprint "eagle-import:AP7366-W5-7")
      (fields (field (name "MFR") "Diodes Inc"))
      (libsource (lib "eagle-import") (part "AP7366-W5-7"))
    )
    (comp (ref "U4")
      (value "AP7366-W5-7")
      (footprint "eagle-import:AP7366-W5-7")
      (fields (field (name "MFR") "Diodes Inc"))
      (libsource (lib "eagle-import") (part "AP7366-W5-7"))
    )
    (comp (ref "U5")
      (value "MICROBUILDER_FT232HQ")
      (footprint "eagle-import:MICROBUILDER_QFN48_8MM")
      (libsource (lib "eagle-import") (part "MICROBUILDER_FT232HQ"))
    )
    (comp (ref "U6")
      (value "MICROCHIP_93LC76B")
      (footprint "eagle-import:MICROCHIP_SOT23-6")
      (fields (field (name "MF") "MICROCHIP") (field (name "MPN") "93LC76BT-I/OT"))
      (libsource (lib "eagle-import") (part "MICROCHIP_9376?BLC"))
    )
    (comp (ref "U7")
      (value "MT25QL128ABA1EW7")
      (footprint "eagle-import:MT25QL128ABA1EW7")
      (libsource (lib "eagle-import") (part "MT25QL128ABA1EW7"))
    )
  )
  (nets
    (net (code "1") (name "+1V2") (class "Default")
      (node (ref "C9") (pin "2") (pinfunction "P$2_2") (pintype "bidirectional"))
      (node (ref "JP3") (pin "1") (pinfunction "1_1") (pintype "passive"))
      (node (ref "JP5") (pin "1") (pinfunction "1_1") (pintype "passive"))
      (node (ref "R5") (pin "1") (pinfunction "P$1_1") (pintype "bidirectional"))
      (node (ref "U4") (pin "5") (pinfunction "OUT_5") (pintype "bidirectional"))
    )
    (net (code "2") (name "+1V2_METERED") (class "Default")
      (node (ref "C26") (pin "1") (pinfunction "1_1") (pintype "passive"))
      (node (ref "C30") (pin "1") (pinfunction "1_1") (pintype "passive"))
      (node (ref "JP5") (pin "3") (pinfunction "3_3") (pintype "passive"))
      (node (ref "R24") (pin "2") (pinfunction "2_2") (pintype "passive"))
      (node (ref "U9") (pin "9") (pinfunction "IN-3_9") (pintype "bidirectional"))
    )
    (net (code "3") (name "+1V8") (class "Default")
      (node (ref "C7") (pin "2") (pinfunction "P$2_2") (pintype "bidirectional"))
      (node (ref "JP14") (pin "1") (pinfunction "1_1") (pintype "passive"))
      (node (ref "JP16") (pin "1") (pinfunction "1_1") (pintype "passive"))
      (node (ref "JP2") (pin "1") (pinfunction "1_1") (pintype "passive"))
      (node (ref "JP20") (pin "1") (pinfunction "1_1") (pintype "passive"))
      (node (ref "JP34") (pin "1") (pinfunction "1_1") (pintype "passive"))
      (node (ref "JP36") (pin "1") (pinfunction "1_1") (pintype "passive"))
      (node (ref "JP9") (pin "1") (pinfunction "1_1") (pintype "passive"))
      (node (ref "R3") (pin "1") (pinfunction "P$1_1") (pintype "bidirectional"))
      (node (ref "U3") (pin "5") (pinfunction "OUT_5") (pintype "bidirectional"))
    )
    (net (code "4") (name "+1V8_METERED") (class "Default")
      (node (ref "C25") (pin "1") (pinfunction "1_1") (pintype "passive"))
      (node (ref "C28") (pin "1") (pinfunction "1_1") (pintype "passive"))
      (node (ref "JP14") (pin "3") (pinfunction "3_3") (pintype "passive"))
      (node (ref "JP16") (pin "3") (pinfunction "3_3") (pintype "passive"))
      (node (ref "JP20") (pin "3") (pinfunction "3_3") (pintype "passive"))
      (node (ref "JP34") (pin "3") (pinfunction "3_3") (pintype "passive"))
      (node (ref "JP36") (pin "3") (pinfunction "3_3") (pintype "passive"))
      (node (ref "JP9") (pin "3") (pinfunction "3_3") (pintype "passive"))
      (node (ref "R23") (pin "2") (pinfunction "2_2") (pintype "passive"))
      (node (ref "U9") (pin "6") (pinfunction "IN-2_6") (pintype "bidirectional"))
    )
    (net (code "5") (name "+2V8") (class "Default")
      (node (ref "C46") (pin "2") (pinfunction "P$2_2") (pintype "bidirectional"))
      (node (ref "JP17") (pin "1") (pinfunction "1_1") (pintype "passive"))
      (node (ref "JP18") (pin "1") (pinfunction "1_1") (pintype "passive"))
      (node (ref "R30") (pin "1") (pinfunction "P$1_1") (pintype "bidirectional"))
      (node (ref "U10") (pin "5") (pinfunction "OUT_5") (pintype "bidirectional"))
    )
    (net (code "6") (name "+2V8_METERED") (class "Default")
      (node (ref "C47") (pin "1") (pinfunction "1_1") (pintype "passive"))
      (node (ref "C48") (pin "1") (pinfunction "1_1") (pintype "passive"))
      (node (ref "JP17") (pin "3") (pinfunction "3_3") (pintype "passive"))
      (node (ref "R32") (pin "2") (pinfunction "2_2") (pintype "passive"))
      (node (ref "U9") (pin "13") (pinfunction "IN-4_13") (pintype "bidirectional"))
    )
    (net (code "7") (name "+3V3") (class "Default")
      (node (ref "C29") (pin "2") (pinfunction "P$2_2") (pintype "bidirectional"))
      (node (ref "C3") (pin "2") (pinfunction "P$2_2") (pintype "bidirectional"))
      (node (ref "C31") (pin "2") (pinfunction "P$2_2") (pintype "bidirectional"))
      (node (ref "JP1") (pin "1") (pinfunction "1_1") (pintype "passive"))
      (node (ref "JP13") (pin "1") (pinfunction "1_1") (pintype "passive"))
      (node (ref "JP19") (pin "1") (pinfunction "1_1") (pintype "passive"))
      (node (ref "JP22") (pin "1") (pinfunction "1_1") (pintype "passive"))
      (node (ref "JP31") (pin "1") (pinfunction "1_1") (pintype "passive"))
      (node (ref "JP32") (pin "1") (pinfunction "1_1") (pintype "passive"))
      (node (ref "JP33") (pin "1") (pinfunction "1_1") (pintype "passive"))
      (node (ref "JP35") (pin "1") (pinfunction "1_1") (pintype "passive"))
      (node (ref "JP37") (pin "1") (pinfunction "1_1") (pintype "passive"))
      (node (ref "JP38") (pin "1") (pinfunction "1_1") (pintype "passive"))
      (node (ref "JP4") (pin "1") (pinfunction "1_1") (pintype "passive"))
      (node (ref "JP6") (pin "1") (pinfunction "1_1") (pintype "passive"))
      (node (ref "JP7") (pin "1") (pinfunction "1_1") (pintype "passive"))
      (node (ref "JP8") (pin "1") (pinfunction "1_1") (pintype "passive"))
      (node (ref "R1") (pin "1") (pinfunction "P$1_1") (pintype "bidirectional"))
      (node (ref "R27") (pin "1") (pinfunction "P$1_1") (pintype "bidirectional"))
      (node (ref "R36") (pin "1") (pinfunction "P$1_1") (pintype "bidirectional"))
      (node (ref "R37") (pin "1") (pinfunction "P$1_1") (pintype "bidirectional"))
      (node (ref "R38") (pin "1") (pinfunction "P$1_1") (pintype "bidirectional"))
      (node (ref "U1") (pin "5") (pinfunction "OUT_5") (pintype "bidirectional"))
      (node (ref "U9") (pin "4") (pinfunction "VS_4") (pintype "bidirectional"))
    )
    (net (code "8") (name "+3V3_METERED") (class "Default")
      (node (ref "C24") (pin "1") (pinfunction "1_1") (pintype "passive"))
      (node (ref "C27") (pin "1") (pinfunction "1_1") (pintype "passive"))
      (node (ref "JP13") (pin "3") (pinfunction "3_3") (pintype "passive"))
      (node (ref "JP19") (pin "3") (pinfunction "3_3") (pintype "passive"))
      (node (ref "JP22") (pin "3") (pinfunction "3_3") (pintype "passive"))
      (node (ref "JP31") (pin "3") (pinfunction "3_3") (pintype "passive"))
      (node (ref "JP32") (pin "3") (pinfunction "3_3") (pintype "passive"))
      (node (ref "JP33") (pin "3") (pinfunction "3_3") (pintype "passive"))
      (node (ref "JP35") (pin "3") (pinfunction "3_3") (pintype "passive"))
      (node (ref "JP37") (pin "3") (pinfunction "3_3") (pintype "passive"))
      (node (ref "JP38") (pin "3") (pinfunction "3_3") (pintype "passive"))
      (node (ref "JP4") (pin "3") (pinfunction "3_3") (pintype "passive"))
      (node (ref "JP6") (pin "3") (pinfunction "3_3") (pintype "passive"))
      (node (ref "JP7") (pin "3") (pinfunction "3_3") (pintype "passive"))
      (node (ref "JP8") (pin "3") (pinfunction "3_3") (pintype "passive"))
      (node (ref "R22") (pin "2") (pinfunction "2_2") (pintype "passive"))
      (node (ref "U9") (pin "2") (pinfunction "IN-1_2") (pintype "bidirectional"))
    )
    (net (code "9") (name "CONFIG_FLASH_+3V3") (class "Default")
      (node (ref "C22") (pin "2") (pinfunction "P$2_2") (pintype "bidirectional"))
      (node (ref "C23") (pin "1") (pinfunction "1_1") (pintype "passive"))
      (node (ref "JP4") (pin "2") (pinfunction "2_2") (pintype "passive"))
      (node (ref "R18") (pin "1") (pinfunction "P$1_1") (pintype "bidirectional"))
      (node (ref "R19") (pin "1") (pinfunction "P$1_1") (pintype "bidirectional"))
      (node (ref "R20") (pin "1") (pinfunction "P$1_1") (pintype "bidirectional"))
      (node (ref "R21") (pin "1") (pinfunction "P$1_1") (pintype "bidirectional"))
      (node (ref "U7") (pin "8") (pinfunction "VCC_8") (pintype "bidirectional"))
    )
    (net (code "10") (name "D+") (class "Default")
      (node (ref "J2") (pin "3") (pinfunction "3_3") (pintype "passive"))
      (node (ref "U5") (pin "7") (pinfunction "USBD+_7") (pintype "bidirectional"))
    )
    (net (code "11") (name "D-") (class "Default")
      (node (ref "J2") (pin "2") (pinfunction "2_2") (pintype "passive"))
      (node (ref "U5") (pin "6") (pinfunction "USBD-_6") (pintype "bidirectional"))
    )
    (net (code "12") (name "FT232_OSC_12M") (class "Default")
      (node (ref "U2") (pin "P$3") (pinfunction "OUT_P$3") (pintype "bidirectional"))
      (node (ref "U5") (pin "1") (pinfunction "OSCIN_1") (pintype "input"))
    )
    (net (code "13") (name "FT232_VCCD") (class "Default")
      (node (ref "C11") (pin "2") (pinfunction "P$2_2") (pintype "bidirectional"))
      (node (ref "C13") (pin "1") (pinfunction "1_1") (pintype "passive"))
      (node (ref "C14") (pin "2") (pinfunction "P$2_2") (pintype "bidirectional"))
      (node (ref "C15") (pin "2") (pinfunction "P$2_2") (pintype "bidirectional"))
      (node (ref "C16") (pin "2") (pinfunction "P$2_2") (pintype "bidirectional"))
      (node (ref "C19") (pin "2") (pinfunction "P$2_2") (pintype "bidirectional"))
      (node (ref "C20") (pin "2") (pinfunction "P$2_2") (pintype "bidirectional"))
      (node (ref "FB1") (pin "1") (pinfunction "P$1_1") (pintype "bidirectional"))
      (node (ref "FB2") (pin "1") (pinfunction "P$1_1") (pintype "bidirectional"))
      (node (ref "LED1") (pin "A") (pinfunction "A_A") (pintype "passive"))
      (node (ref "LED2") (pin "A") (pinfunction "A_A") (pintype "passive"))
      (node (ref "R10") (pin "1") (pinfunction "P$1_1") (pintype "bidirectional"))
      (node (ref "R11") (pin "1") (pinfunction "P$1_1") (pintype "bidirectional"))
      (node (ref "R12") (pin "1") (pinfunction "P$1_1") (pintype "bidirectional"))
      (node (ref "R13") (pin "1") (pinfunction "P$1_1") (pintype "bidirectional"))
      (node (ref "R7") (pin "1") (pinfunction "P$1_1") (pintype "bidirectional"))
      (node (ref "U2") (pin "P$4") (pinfunction "VCC_P$4") (pintype "bidirectional"))
      (node (ref "U5") (pin "12") (pinfunction "VCCIO_12") (pintype "power_in"))
      (node (ref "U5") (pin "24") (pinfunction "VCCIO_24") (pintype "power_in"))
      (node (ref "U5") (pin "39") (pinfunction "VCCD_39") (pintype "power_in"))
      (node (ref "U5") (pin "46") (pinfunction "VCCIO_46") (pintype "power_in"))
      (node (ref "U6") (pin "6") (pinfunction "VCC_6") (pintype "power_in"))
    )
    (net (code "14") (name "GND") (class "Default")
      (node (ref "C1") (pin "1") (pinfunction "P$1_1") (pintype "bidirectional"))
      (node (ref "C10") (pin "1") (pinfunction "P$1_1") (pintype "bidirectional"))
      (node (ref "C11") (pin "1") (pinfunction "P$1_1") (pintype "bidirectional"))
      (node (ref "C12") (pin "2") (pinfunction "2_2") (pintype "passive"))
      (node (ref "C13") (pin "2") (pinfunction "2_2") (pintype "passive"))
      (node (ref "C14") (pin "1") (pinfunction "P$1_1") (pintype "bidirectional"))
      (node (ref "C15") (pin "1") (pinfunction "P$1_1") (pintype "bidirectional"))
      (node (ref "C16") (pin "1") (pinfunction "P$1_1") (pintype "bidirectional"))
      (node (ref "C17") (pin "1") (pinfunction "P$1_1") (pintype "bidirectional"))
      (node (ref "C18") (pin "1") (pinfunction "P$1_1") (pintype "bidirectional"))
      (node (ref "C19") (pin "1") (pinfunction "P$1_1") (pintype "bidirectional"))
      (node (ref "C2") (pin "1") (pinfunction "P$1_1") (pintype "bidirectional"))
      (node (ref "C20") (pin "1") (pinfunction "P$1_1") (pintype "bidirectional"))
      (node (ref "C21") (pin "1") (pinfunction "P$1_1") (pintype "bidirectional"))
      (node (ref "C22") (pin "1") (pinfunction "P$1_1") (pintype "bidirectional"))
      (node (ref "C23") (pin "2") (pinfunction "2_2") (pintype "passive"))
      (node (ref "C24") (pin "2") (pinfunction "2_2") (pintype "passive"))
      (node (ref "C25") (pin "2") (pinfunction "2_2") (pintype "passive"))
      (node (ref "C26") (pin "2") (pinfunction "2_2") (pintype "passive"))
      (node (ref "C27") (pin "2") (pinfunction "2_2") (pintype "passive"))
      (node (ref "C28") (pin "2") (pinfunction "2_2") (pintype "passive"))
      (node (ref "C29") (pin "1") (pinfunction "P$1_1") (pintype "bidirectional"))
      (node (ref "C3") (pin "1") (pinfunction "P$1_1") (pintype "bidirectional"))
      (node (ref "C30") (pin "2") (pinfunction "2_2") (pintype "passive"))
      (node (ref "C31") (pin "1") (pinfunction "P$1_1") (pintype "bidirectional"))
      (node (ref "C32") (pin "1") (pinfunction "P$1_1") (pintype "bidirectional"))
      (node (ref "C33") (pin "2") (pinfunction "2_2") (pintype "passive"))
      (node (ref "C34") (pin "1") (pinfunction "P$1_1") (pintype "bidirectional"))
      (node (ref "C35") (pin "1") (pinfunction "P$1_1") (pintype "bidirectional"))
      (node (ref "C36") (pin "1") (pinfunction "P$1_1") (pintype "bidirectional"))
      (node (ref "C37") (pin "1") (pinfunction "P$1_1") (pintype "bidirectional"))
      (node (ref "C38") (pin "1") (pinfunction "P$1_1") (pintype "bidirectional"))
      (node (ref "C39") (pin "1") (pinfunction "P$1_1") (pintype "bidirectional"))
      (node (ref "C4") (pin "1") (pinfunction "P$1_1") (pintype "bidirectional"))
      (node (ref "C40") (pin "2") (pinfunction "2_2") (pintype "passive"))
      (node (ref "C41") (pin "1") (pinfunction "P$1_1") (pintype "bidirectional"))
      (node (ref "C42") (pin "2") (pinfunction "2_2") (pintype "passive"))
      (node (ref "C43") (pin "1") (pinfunction "P$1_1") (pintype "bidirectional"))
      (node (ref "C44") (pin "2") (pinfunction "2_2") (pintype "passive"))
      (node (ref "C45") (pin "1") (pinfunction "P$1_1") (pintype "bidirectional"))
      (node (ref "C46") (pin "1") (pinfunction "P$1_1") (pintype "bidirectional"))
      (node (ref "C47") (pin "2") (pinfunction "2_2") (pintype "passive"))
      (node (ref "C48") (pin "2") (pinfunction "2_2") (pintype "passive"))
      (node (ref "C49") (pin "1") (pinfunction "P$1_1") (pintype "bidirectional"))
      (node (ref "C5") (pin "1") (pinfunction "P$1_1") (pintype "bidirectional"))
      (node (ref "C50") (pin "1") (pinfunction "P$1_1") (pintype "bidirectional"))
      (node (ref "C51") (pin "1") (pinfunction "P$1_1") (pintype "bidirectional"))
      (node (ref "C52") (pin "1") (pinfunction "P$1_1") (pintype "bidirectional"))
      (node (ref "C53") (pin "1") (pinfunction "P$1_1") (pintype "bidirectional"))
      (node (ref "C54") (pin "1") (pinfunction "P$1_1") (pintype "bidirectional"))
      (node (ref "C6") (pin "1") (pinfunction "P$1_1") (pintype "bidirectional"))
      (node (ref "C7") (pin "1") (pinfunction "P$1_1") (pintype "bidirectional"))
      (node (ref "C8") (pin "1") (pinfunction "P$1_1") (pintype "bidirectional"))
      (node (ref "C9") (pin "1") (pinfunction "P$1_1") (pintype "bidirectional"))
      (node (ref "J1") (pin "P$15") (pinfunction "P$15_P$15") (pintype "bidirectional"))
      (node (ref "J1") (pin "P$2") (pinfunction "P$2_P$2") (pintype "bidirectional"))
      (node (ref "J2") (pin "5") (pinfunction "5_5") (pintype "passive"))
      (node (ref "J2") (pin "S1") (pinfunction "SHIELD_S1") (pintype "passive"))
      (node (ref "J2") (pin "S2") (pinfunction "SHIELD_S2") (pintype "passive"))
      (node (ref "J2") (pin "S3") (pinfunction "SHIELD_S3") (pintype "passive"))
      (node (ref "J2") (pin "S4") (pinfunction "SHIELD_S4") (pintype "passive"))
      (node (ref "J2") (pin "S5") (pinfunction "SHIELD_S5") (pintype "passive"))
      (node (ref "J2") (pin "S6") (pinfunction "SHIELD_S6") (pintype "passive"))
      (node (ref "J3") (pin "P$1") (pinfunction "P$1_P$1") (pintype "bidirectional"))
      (node (ref "JP10") (pin "2") (pinfunction "2_2") (pintype "passive"))
      (node (ref "JP11") (pin "2") (pinfunction "2_2") (pintype "passive"))
      (node (ref "JP12") (pin "2") (pinfunction "2_2") (pintype "passive"))
      (node (ref "JP15") (pin "2") (pinfunction "2_2") (pintype "passive"))
      (node (ref "JP21") (pin "2") (pinfunction "2_2") (pintype "passive"))
      (node (ref "JP23") (pin "2") (pinfunction "2_2") (pintype "passive"))
      (node (ref "JP23") (pin "4") (pinfunction "4_4") (pintype "passive"))
      (node (ref "JP23") (pin "6") (pinfunction "6_6") (pintype "passive"))
      (node (ref "JP23") (pin "7") (pinfunction "7_7") (pintype "passive"))
      (node (ref "JP23") (pin "8") (pinfunction "8_8") (pintype "passive"))
      (node (ref "JP24") (pin "2") (pinfunction "2_2") (pintype "passive"))
      (node (ref "JP24") (pin "4") (pinfunction "4_4") (pintype "passive"))
      (node (ref "JP24") (pin "6") (pinfunction "6_6") (pintype "passive"))
      (node (ref "JP24") (pin "7") (pinfunction "7_7") (pintype "passive"))
      (node (ref "JP24") (pin "8") (pinfunction "8_8") (pintype "passive"))
      (node (ref "JP25") (pin "2") (pinfunction "2_2") (pintype "passive"))
      (node (ref "JP25") (pin "4") (pinfunction "4_4") (pintype "passive"))
      (node (ref "JP25") (pin "6") (pinfunction "6_6") (pintype "passive"))
      (node (ref "JP25") (pin "8") (pinfunction "8_8") (pintype "passive"))
      (node (ref "JP26") (pin "2") (pinfunction "2_2") (pintype "passive"))
      (node (ref "JP26") (pin "4") (pinfunction "4_4") (pintype "passive"))
      (node (ref "JP26") (pin "6") (pinfunction "6_6") (pintype "passive"))
      (node (ref "JP26") (pin "8") (pinfunction "8_8") (pintype "passive"))
      (node (ref "JP27") (pin "2") (pinfunction "2_2") (pintype "passive"))
      (node (ref "JP27") (pin "4") (pinfunction "4_4") (pintype "passive"))
      (node (ref "JP27") (pin "6") (pinfunction "6_6") (pintype "passive"))
      (node (ref "JP27") (pin "7") (pinfunction "7_7") (pintype "passive"))
      (node (ref "JP27") (pin "8") (pinfunction "8_8") (pintype "passive"))
      (node (ref "JP28") (pin "2") (pinfunction "2_2") (pintype "passive"))
      (node (ref "JP28") (pin "4") (pinfunction "4_4") (pintype "passive"))
      (node (ref "JP28") (pin "6") (pinfunction "6_6") (pintype "passive"))
      (node (ref "JP28") (pin "7") (pinfunction "7_7") (pintype "passive"))
      (node (ref "JP28") (pin "8") (pinfunction "8_8") (pintype "passive"))
      (node (ref "JP29") (pin "2") (pinfunction "2_2") (pintype "passive"))
      (node (ref "JP29") (pin "4") (pinfunction "4_4") (pintype "passive"))
      (node (ref "JP29") (pin "6") (pinfunction "6_6") (pintype "passive"))
      (node (ref "JP29") (pin "8") (pinfunction "8_8") (pintype "passive"))
      (node (ref "JP30") (pin "2") (pinfunction "2_2") (pintype "passive"))
      (node (ref "JP30") (pin "4") (pinfunction "4_4") (pintype "passive"))
      (node (ref "JP30") (pin "6") (pinfunction "6_6") (pintype "passive"))
      (node (ref "JP30") (pin "8") (pinfunction "8_8") (pintype "passive"))
      (node (ref "JP39") (pin "10") (pinfunction "10_10") (pintype "passive"))
      (node (ref "JP39") (pin "12") (pinfunction "12_12") (pintype "passive"))
      (node (ref "JP39") (pin "14") (pinfunction "14_14") (pintype "passive"))
      (node (ref "JP39") (pin "16") (pinfunction "16_16") (pintype "passive"))
      (node (ref "JP39") (pin "18") (pinfunction "18_18") (pintype "passive"))
      (node (ref "JP39") (pin "2") (pinfunction "2_2") (pintype "passive"))
      (node (ref "JP39") (pin "20") (pinfunction "20_20") (pintype "passive"))
      (node (ref "JP39") (pin "22") (pinfunction "22_22") (pintype "passive"))
      (node (ref "JP39") (pin "24") (pinfunction "24_24") (pintype "passive"))
      (node (ref "JP39") (pin "26") (pinfunction "26_26") (pintype "passive"))
      (node (ref "JP39") (pin "28") (pinfunction "28_28") (pintype "passive"))
      (node (ref "JP39") (pin "30") (pinfunction "30_30") (pintype "passive"))
      (node (ref "JP39") (pin "32") (pinfunction "32_32") (pintype "passive"))
      (node (ref "JP39") (pin "34") (pinfunction "34_34") (pintype "passive"))
      (node (ref "JP39") (pin "4") (pinfunction "4_4") (pintype "passive"))
      (node (ref "JP39") (pin "6") (pinfunction "6_6") (pintype "passive"))
      (node (ref "JP39") (pin "8") (pinfunction "8_8") (pintype "passive"))
      (node (ref "JP40") (pin "10") (pinfunction "10_10") (pintype "passive"))
      (node (ref "JP40") (pin "12") (pinfunction "12_12") (pintype "passive"))
      (node (ref "JP40") (pin "14") (pinfunction "14_14") (pintype "passive"))
      (node (ref "JP40") (pin "16") (pinfunction "16_16") (pintype "passive"))
      (node (ref "JP40") (pin "18") (pinfunction "18_18") (pintype "passive"))
      (node (ref "JP40") (pin "2") (pinfunction "2_2") (pintype "passive"))
      (node (ref "JP40") (pin "20") (pinfunction "20_20") (pintype "passive"))
      (node (ref "JP40") (pin "22") (pinfunction "22_22") (pintype "passive"))
      (node (ref "JP40") (pin "24") (pinfunction "24_24") (pintype "passive"))
      (node (ref "JP40") (pin "26") (pinfunction "26_26") (pintype "passive"))
      (node (ref "JP40") (pin "28") (pinfunction "28_28") (pintype "passive"))
      (node (ref "JP40") (pin "30") (pinfunction "30_30") (pintype "passive"))
      (node (ref "JP40") (pin "4") (pinfunction "4_4") (pintype "passive"))
      (node (ref "JP40") (pin "6") (pinfunction "6_6") (pintype "passive"))
      (node (ref "JP40") (pin "8") (pinfunction "8_8") (pintype "passive"))
      (node (ref "JP41") (pin "10") (pinfunction "10_10") (pintype "passive"))
      (node (ref "JP41") (pin "12") (pinfunction "12_12") (pintype "passive"))
      (node (ref "JP41") (pin "14") (pinfunction "14_14") (pintype "passive"))
      (node (ref "JP41") (pin "16") (pinfunction "16_16") (pintype "passive"))
      (node (ref "JP41") (pin "2") (pinfunction "2_2") (pintype "passive"))
      (node (ref "JP41") (pin "4") (pinfunction "4_4") (pintype "passive"))
      (node (ref "JP41") (pin "6") (pinfunction "6_6") (pintype "passive"))
      (node (ref "JP41") (pin "8") (pinfunction "8_8") (pintype "passive"))
      (node (ref "R17") (pin "2") (pinfunction "P$2_2") (pintype "bidirectional"))
      (node (ref "R2") (pin "2") (pinfunction "P$2_2") (pintype "bidirectional"))
      (node (ref "R33") (pin "2") (pinfunction "P$2_2") (pintype "bidirectional"))
      (node (ref "R4") (pin "2") (pinfunction "P$2_2") (pintype "bidirectional"))
      (node (ref "R6") (pin "2") (pinfunction "P$2_2") (pintype "bidirectional"))
      (node (ref "R8") (pin "1") (pinfunction "P$1_1") (pintype "bidirectional"))
      (node (ref "SW1") (pin "P$3") (pinfunction "P$3_P$3") (pintype "bidirectional"))
      (node (ref "SW1") (pin "P$4") (pinfunction "P$4_P$4") (pintype "bidirectional"))
      (node (ref "SW2") (pin "P$3") (pinfunction "P$3_P$3") (pintype "bidirectional"))
      (node (ref "SW2") (pin "P$4") (pinfunction "P$4_P$4") (pintype "bidirectional"))
      (node (ref "SW3") (pin "P$3") (pinfunction "P$3_P$3") (pintype "bidirectional"))
      (node (ref "SW3") (pin "P$4") (pinfunction "P$4_P$4") (pintype "bidirectional"))
      (node (ref "U1") (pin "2") (pinfunction "GND_2") (pintype "bidirectional"))
      (node (ref "U10") (pin "2") (pinfunction "GND_2") (pintype "bidirectional"))
      (node (ref "U11") (pin "P$2") (pinfunction "GND_P$2") (pintype "bidirectional"))
      (node (ref "U12") (pin "P$2") (pinfunction "SEL_P$2") (pintype "bidirectional"))
      (node (ref "U12") (pin "P$3@0") (pinfunction "GND_P$3@0") (pintype "bidirectional"))
      (node (ref "U12") (pin "P$3@1") (pinfunction "GND_P$3@1") (pintype "bidirectional"))
      (node (ref "U12") (pin "P$3@2") (pinfunction "GND_P$3@2") (pintype "bidirectional"))
      (node (ref "U12") (pin "P$3@3") (pinfunction "GND_P$3@3") (pintype "bidirectional"))
      (node (ref "U13") (pin "P$3@0") (pinfunction "GND_P$3@0") (pintype "bidirectional"))
      (node (ref "U13") (pin "P$3@1") (pinfunction "GND_P$3@1") (pintype "bidirectional"))
      (node (ref "U13") (pin "P$3@2") (pinfunction "GND_P$3@2") (pintype "bidirectional"))
      (node (ref "U13") (pin "P$3@3") (pinfunction "GND_P$3@3") (pintype "bidirectional"))
      (node (ref "U2") (pin "P$2") (pinfunction "GND_P$2") (pintype "bidirectional"))
      (node (ref "U3") (pin "2") (pinfunction "GND_2") (pintype "bidirectional"))
      (node (ref "U4") (pin "2") (pinfunction "GND_2") (pintype "bidirectional"))
      (node (ref "U5") (pin "10") (pinfunction "GND_10") (pintype "power_in"))
      (node (ref "U5") (pin "11") (pinfunction "GND_11") (pintype "power_in"))
      (node (ref "U5") (pin "22") (pinfunction "GND_22") (pintype "power_in"))
      (node (ref "U5") (pin "23") (pinfunction "GND_23") (pintype "power_in"))
      (node (ref "U5") (pin "35") (pinfunction "GND_35") (pintype "power_in"))
      (node (ref "U5") (pin "36") (pinfunction "GND_36") (pintype "power_in"))
      (node (ref "U5") (pin "4") (pinfunction "AGND_4") (pintype "power_in"))
      (node (ref "U5") (pin "41") (pinfunction "AGND_41") (pintype "power_in"))
      (node (ref "U5") (pin "42") (pinfunction "TEST_42") (pintype "input"))
      (node (ref "U5") (pin "47") (pinfunction "GND_47") (pintype "power_in"))
      (node (ref "U5") (pin "48") (pinfunction "GND_48") (pintype "power_in"))
      (node (ref "U5") (pin "9") (pinfunction "AGND_9") (pintype "power_in"))
      (node (ref "U5") (pin "THERMAL") (pinfunction "PAD_THERMAL") (pintype "passive"))
      (node (ref "U6") (pin "2") (pinfunction "GND_2") (pintype "power_in"))
      (node (ref "U7") (pin "4") (pinfunction "VSS_4") (pintype "bidirectional"))
      (node (ref "U7") (pin "9") (pinfunction "PAD_9") (pintype "bidirectional"))
      (node (ref "U8") (pin "49") (pinfunction "49_49") (pintype "bidirectional"))
      (node (ref "U9") (pin "11") (pinfunction "GND_11") (pintype "bidirectional"))
    )
    (net (code "15") (name "HM01B0_+1V8") (class "Default")
      (node (ref "J1") (pin "P$10") (pinfunction "P$10_P$10") (pintype "bidirectional"))
      (node (ref "JP16") (pin "2") (pinfunction "2_2") (pintype "passive"))
      (node (ref "R28") (pin "1") (pinfunction "P$1_1") (pintype "bidirectional"))
      (node (ref "R29") (pin "1") (pinfunction "P$1_1") (pintype "bidirectional"))
    )
    (net (code "16") (name "HM01B0_+2V8") (class "Default")
      (node (ref "J1") (pin "P$11") (pinfunction "P$11_P$11") (pintype "bidirectional"))
      (node (ref "J1") (pin "P$4") (pinfunction "P$4_P$4") (pintype "bidirectional"))
      (node (ref "JP17") (pin "2") (pinfunction "2_2") (pintype "passive"))
    )
    (net (code "17") (name "HM01B0_D0") (class "Default")
      (node (ref "J1") (pin "P$14") (pinfunction "P$14_P$14") (pintype "bidirectional"))
      (node (ref "SJ9") (pin "1") (pinfunction "1_1") (pintype "passive"))
      (node (ref "U8") (pin "35") (pinfunction "35_35") (pintype "bidirectional"))
    )
    (net (code "18") (name "HM01B0_D1") (class "Default")
      (node (ref "J1") (pin "P$3") (pinfunction "P$3_P$3") (pintype "bidirectional"))
      (node (ref "SJ1") (pin "1") (pinfunction "1_1") (pintype "passive"))
      (node (ref "U8") (pin "23") (pinfunction "23_23") (pintype "bidirectional"))
    )
    (net (code "19") (name "HM01B0_D2") (class "Default")
      (node (ref "J1") (pin "P$9") (pinfunction "P$9_P$9") (pintype "bidirectional"))
      (node (ref "SJ6") (pin "1") (pinfunction "1_1") (pintype "passive"))
      (node (ref "U8") (pin "31") (pinfunction "31_31") (pintype "bidirectional"))
    )
    (net (code "20") (name "HM01B0_D3") (class "Default")
      (node (ref "J1") (pin "P$5") (pinfunction "P$5_P$5") (pintype "bidirectional"))
      (node (ref "SJ2") (pin "1") (pinfunction "1_1") (pintype "passive"))
      (node (ref "U8") (pin "25") (pinfunction "25_25") (pintype "bidirectional"))
    )
    (net (code "21") (name "HM01B0_D4") (class "Default")
      (node (ref "J1") (pin "P$12") (pinfunction "P$12_P$12") (pintype "bidirectional"))
      (node (ref "SJ7") (pin "1") (pinfunction "1_1") (pintype "passive"))
      (node (ref "U8") (pin "32") (pinfunction "32_32") (pintype "bidirectional"))
    )
    (net (code "22") (name "HM01B0_D5") (class "Default")
      (node (ref "J1") (pin "P$20") (pinfunction "P$20_P$20") (pintype "bidirectional"))
      (node (ref "SJ14") (pin "1") (pinfunction "1_1") (pintype "passive"))
      (node (ref "U8") (pin "40") (pinfunction "40_40") (pintype "bidirectional"))
    )
    (net (code "23") (name "HM01B0_D6") (class "Default")
      (node (ref "J1") (pin "P$19") (pinfunction "P$19_P$19") (pintype "bidirectional"))
      (node (ref "SJ13") (pin "1") (pinfunction "1_1") (pintype "passive"))
      (node (ref "U8") (pin "39") (pinfunction "39_39") (pintype "bidirectional"))
    )
    (net (code "24") (name "HM01B0_D7") (class "Default")
      (node (ref "J1") (pin "P$13") (pinfunction "P$13_P$13") (pintype "bidirectional"))
      (node (ref "SJ8") (pin "1") (pinfunction "1_1") (pintype "passive"))
      (node (ref "U8") (pin "34") (pinfunction "34_34") (pintype "bidirectional"))
    )
    (net (code "25") (name "HM01B0_HS") (class "Default")
      (node (ref "J1") (pin "P$16") (pinfunction "P$16_P$16") (pintype "bidirectional"))
      (node (ref "SJ10") (pin "1") (pinfunction "1_1") (pintype "passive"))
      (node (ref "U8") (pin "36") (pinfunction "36_36") (pintype "bidirectional"))
    )
    (net (code "26") (name "HM01B0_INT") (class "Default")
      (node (ref "J1") (pin "P$18") (pinfunction "P$18_P$18") (pintype "bidirectional"))
      (node (ref "SJ12") (pin "1") (pinfunction "1_1") (pintype "passive"))
      (node (ref "SW3") (pin "P$1") (pinfunction "P$1_P$1") (pintype "bidirectional"))
      (node (ref "SW3") (pin "P$2") (pinfunction "P$2_P$2") (pintype "bidirectional"))
      (node (ref "U8") (pin "38") (pinfunction "38_38") (pintype "bidirectional"))
    )
    (net (code "27") (name "HM01B0_MCK") (class "Default")
      (node (ref "J1") (pin "P$8") (pinfunction "P$8_P$8") (pintype "bidirectional"))
      (node (ref "SJ5") (pin "1") (pinfunction "1_1") (pintype "passive"))
      (node (ref "U8") (pin "28") (pinfunction "28_28") (pintype "bidirectional"))
    )
    (net (code "28") (name "HM01B0_PCLK") (class "Default")
      (node (ref "J1") (pin "P$17") (pinfunction "P$17_P$17") (pintype "bidirectional"))
      (node (ref "SJ11") (pin "1") (pinfunction "1_1") (pintype "passive"))
      (node (ref "U8") (pin "37") (pinfunction "37_37") (pintype "bidirectional"))
    )
    (net (code "29") (name "HM01B0_SCL") (class "Default")
      (node (ref "J1") (pin "P$21") (pinfunction "P$21_P$21") (pintype "bidirectional"))
      (node (ref "R29") (pin "2") (pinfunction "P$2_2") (pintype "bidirectional"))
      (node (ref "SJ15") (pin "1") (pinfunction "1_1") (pintype "passive"))
      (node (ref "U8") (pin "41") (pinfunction "41_41") (pintype "bidirectional"))
    )
    (net (code "30") (name "HM01B0_SDA") (class "Default")
      (node (ref "J1") (pin "P$22") (pinfunction "P$22_P$22") (pintype "bidirectional"))
      (node (ref "R28") (pin "2") (pinfunction "P$2_2") (pintype "bidirectional"))
      (node (ref "SJ16") (pin "1") (pinfunction "1_1") (pintype "passive"))
      (node (ref "U8") (pin "42") (pinfunction "42_42") (pintype "bidirectional"))
    )
    (net (code "31") (name "HM01B0_TRIG") (class "Default")
      (node (ref "J1") (pin "P$7") (pinfunction "P$7_P$7") (pintype "bidirectional"))
      (node (ref "LED5") (pin "C") (pinfunction "C_C") (pintype "passive"))
      (node (ref "SJ4") (pin "1") (pinfunction "1_1") (pintype "passive"))
      (node (ref "U8") (pin "27") (pinfunction "27_27") (pintype "bidirectional"))
    )
    (net (code "32") (name "HM01B0_VS") (class "Default")
      (node (ref "J1") (pin "P$6") (pinfunction "P$6_P$6") (pintype "bidirectional"))
      (node (ref "SJ3") (pin "1") (pinfunction "1_1") (pintype "passive"))
      (node (ref "U8") (pin "26") (pinfunction "26_26") (pintype "bidirectional"))
    )
    (net (code "33") (name "I2S_DATA") (class "Default")
      (node (ref "JP40") (pin "27") (pinfunction "27_27") (pintype "passive"))
      (node (ref "U12") (pin "P$6") (pinfunction "DATA_P$6") (pintype "bidirectional"))
      (node (ref "U13") (pin "P$6") (pinfunction "DATA_P$6") (pintype "bidirectional"))
      (node (ref "U8") (pin "20") (pinfunction "20_20") (pintype "bidirectional"))
    )
    (net (code "34") (name "I2S_WS") (class "Default")
      (node (ref "JP40") (pin "29") (pinfunction "29_29") (pintype "passive"))
      (node (ref "U12") (pin "P$1") (pinfunction "WS_P$1") (pintype "bidirectional"))
      (node (ref "U13") (pin "P$1") (pinfunction "WS_P$1") (pintype "bidirectional"))
      (node (ref "U8") (pin "21") (pinfunction "21_21") (pintype "bidirectional"))
    )
    (net (code "35") (name "ICE40_+1V2") (class "Default")
      (node (ref "C34") (pin "2") (pinfunction "P$2_2") (pintype "bidirectional"))
      (node (ref "C35") (pin "2") (pinfunction "P$2_2") (pintype "bidirectional"))
      (node (ref "C36") (pin "2") (pinfunction "P$2_2") (pintype "bidirectional"))
      (node (ref "C37") (pin "2") (pinfunction "P$2_2") (pintype "bidirectional"))
      (node (ref "JP5") (pin "2") (pinfunction "2_2") (pintype "passive"))
      (node (ref "R25") (pin "1") (pinfunction "P$1_1") (pintype "bidirectional"))
      (node (ref "U8") (pin "30") (pinfunction "30_30") (pintype "bidirectional"))
      (node (ref "U8") (pin "5") (pinfunction "5_5") (pintype "bidirectional"))
    )
    (net (code "36") (name "ICE40_CRESETB") (class "Default")
      (node (ref "C54") (pin "2") (pinfunction "P$2_2") (pintype "bidirectional"))
      (node (ref "R26") (pin "2") (pinfunction "P$2_2") (pintype "bidirectional"))
      (node (ref "SW1") (pin "P$1") (pinfunction "P$1_P$1") (pintype "bidirectional"))
      (node (ref "SW1") (pin "P$2") (pinfunction "P$2_P$2") (pintype "bidirectional"))
      (node (ref "U5") (pin "20") (pinfunction "ADBUS7/RI#_20") (pintype "input"))
      (node (ref "U8") (pin "8") (pinfunction "8_8") (pintype "bidirectional"))
    )
    (net (code "37") (name "ICE40_FLASH_CIPO") (class "Default")
      (node (ref "JP40") (pin "21") (pinfunction "21_21") (pintype "passive"))
      (node (ref "LED3") (pin "C") (pinfunction "C_C") (pintype "passive"))
      (node (ref "U5") (pin "15") (pinfunction "ADBUS2/RTS#_15") (pintype "output"))
      (node (ref "U7") (pin "2") (pinfunction "DQ1_2") (pintype "bidirectional"))
      (node (ref "U8") (pin "17") (pinfunction "17_17") (pintype "bidirectional"))
    )
    (net (code "38") (name "ICE40_FLASH_COPI") (class "Default")
      (node (ref "JP40") (pin "15") (pinfunction "15_15") (pintype "passive"))
      (node (ref "LED4") (pin "C") (pinfunction "C_C") (pintype "passive"))
      (node (ref "U5") (pin "14") (pinfunction "ADBUS1/RXD_14") (pintype "input"))
      (node (ref "U7") (pin "5") (pinfunction "DQ0_5") (pintype "bidirectional"))
      (node (ref "U8") (pin "14") (pinfunction "14_14") (pintype "bidirectional"))
    )
    (net (code "39") (name "ICE40_FLASH_PS") (class "Default")
      (node (ref "JP40") (pin "19") (pinfunction "19_19") (pintype "passive"))
      (node (ref "R19") (pin "2") (pinfunction "P$2_2") (pintype "bidirectional"))
      (node (ref "U5") (pin "17") (pinfunction "ADBUS4/DTR#_17") (pintype "output"))
      (node (ref "U7") (pin "1") (pinfunction "S#_1") (pintype "bidirectional"))
      (node (ref "U8") (pin "16") (pinfunction "16_16") (pintype "bidirectional"))
    )
    (net (code "40") (name "ICE40_FLASH_SCK") (class "Default")
      (node (ref "JP40") (pin "17") (pinfunction "17_17") (pintype "passive"))
      (node (ref "R18") (pin "2") (pinfunction "P$2_2") (pintype "bidirectional"))
      (node (ref "U12") (pin "P$4") (pinfunction "BLK_P$4") (pintype "bidirectional"))
      (node (ref "U13") (pin "P$4") (pinfunction "BLK_P$4") (pintype "bidirectional"))
      (node (ref "U5") (pin "13") (pinfunction "ADBUS0/TXD_13") (pintype "output"))
      (node (ref "U7") (pin "6") (pinfunction "C_6") (pintype "bidirectional"))
      (node (ref "U8") (pin "15") (pinfunction "15_15") (pintype "bidirectional"))
    )
    (net (code "41") (name "ICE40_GPIO4") (class "Default")
      (node (ref "JP41") (pin "15") (pinfunction "15_15") (pintype "passive"))
      (node (ref "LED6") (pin "C") (pinfunction "C_C") (pintype "passive"))
      (node (ref "U8") (pin "4") (pinfunction "4_4") (pintype "bidirectional"))
    )
    (net (code "42") (name "ICE40_GPIO43") (class "Default")
      (node (ref "SJ17") (pin "1") (pinfunction "1_1") (pintype "passive"))
      (node (ref "SW2") (pin "P$1") (pinfunction "P$1_P$1") (pintype "bidirectional"))
      (node (ref "SW2") (pin "P$2") (pinfunction "P$2_P$2") (pintype "bidirectional"))
      (node (ref "U8") (pin "43") (pinfunction "43_43") (pintype "bidirectional"))
    )
    (net (code "43") (name "ICE40_OSC_12M") (class "Default")
      (node (ref "JP41") (pin "1") (pinfunction "1_1") (pintype "passive"))
      (node (ref "U11") (pin "P$3") (pinfunction "OUT_P$3") (pintype "bidirectional"))
      (node (ref "U8") (pin "44") (pinfunction "44_44") (pintype "bidirectional"))
    )
    (net (code "44") (name "ICE40_OSC_VCC") (class "Default")
      (node (ref "C49") (pin "2") (pinfunction "P$2_2") (pintype "bidirectional"))
      (node (ref "JP19") (pin "2") (pinfunction "2_2") (pintype "passive"))
      (node (ref "JP20") (pin "2") (pinfunction "2_2") (pintype "passive"))
      (node (ref "R31") (pin "1") (pinfunction "P$1_1") (pintype "bidirectional"))
      (node (ref "U11") (pin "P$4") (pinfunction "VCC_P$4") (pintype "bidirectional"))
    )
    (net (code "45") (name "ICE40_SPI_VCCIO1") (class "Default")
      (node (ref "C39") (pin "2") (pinfunction "P$2_2") (pintype "bidirectional"))
      (node (ref "C40") (pin "1") (pinfunction "1_1") (pintype "passive"))
      (node (ref "JP7") (pin "2") (pinfunction "2_2") (pintype "passive"))
      (node (ref "R26") (pin "1") (pinfunction "P$1_1") (pintype "bidirectional"))
      (node (ref "U8") (pin "22") (pinfunction "22_22") (pintype "bidirectional"))
    )
    (net (code "46") (name "ICE40_VCCIO0") (class "Default")
      (node (ref "C41") (pin "2") (pinfunction "P$2_2") (pintype "bidirectional"))
      (node (ref "C42") (pin "1") (pinfunction "1_1") (pintype "passive"))
      (node (ref "JP8") (pin "2") (pinfunction "2_2") (pintype "passive"))
      (node (ref "JP9") (pin "2") (pinfunction "2_2") (pintype "passive"))
      (node (ref "U8") (pin "33") (pinfunction "33_33") (pintype "bidirectional"))
    )
    (net (code "47") (name "ICE40_VCCIO2") (class "Default")
      (node (ref "C43") (pin "2") (pinfunction "P$2_2") (pintype "bidirectional"))
      (node (ref "C44") (pin "1") (pinfunction "1_1") (pintype "passive"))
      (node (ref "JP13") (pin "2") (pinfunction "2_2") (pintype "passive"))
      (node (ref "JP14") (pin "2") (pinfunction "2_2") (pintype "passive"))
      (node (ref "U8") (pin "1") (pinfunction "1_1") (pintype "bidirectional"))
    )
    (net (code "48") (name "ICE40_VPP2V5_+3V3") (class "Default")
      (node (ref "C38") (pin "2") (pinfunction "P$2_2") (pintype "bidirectional"))
      (node (ref "JP6") (pin "2") (pinfunction "2_2") (pintype "passive"))
      (node (ref "U8") (pin "24") (pinfunction "24_24") (pintype "bidirectional"))
    )
    (net (code "49") (name "MEM1_CIPO") (class "Default")
      (node (ref "JP23") (pin "3") (pinfunction "3_3") (pintype "passive"))
      (node (ref "JP24") (pin "3") (pinfunction "3_3") (pintype "passive"))
      (node (ref "JP40") (pin "9") (pinfunction "9_9") (pintype "passive"))
      (node (ref "U8") (pin "11") (pinfunction "11_11") (pintype "bidirectional"))
    )
    (net (code "50") (name "MEM1_COPI") (class "Default")
      (node (ref "JP25") (pin "7") (pinfunction "7_7") (pintype "passive"))
      (node (ref "JP26") (pin "7") (pinfunction "7_7") (pintype "passive"))
      (node (ref "JP40") (pin "25") (pinfunction "25_25") (pintype "passive"))
      (node (ref "U8") (pin "19") (pinfunction "19_19") (pintype "bidirectional"))
    )
    (net (code "51") (name "MEM1_PS1") (class "Default")
      (node (ref "JP23") (pin "1") (pinfunction "1_1") (pintype "passive"))
      (node (ref "JP40") (pin "5") (pinfunction "5_5") (pintype "passive"))
      (node (ref "U8") (pin "9") (pinfunction "9_9") (pintype "bidirectional"))
    )
    (net (code "52") (name "MEM1_PS2") (class "Default")
      (node (ref "JP24") (pin "1") (pinfunction "1_1") (pintype "passive"))
      (node (ref "JP40") (pin "7") (pinfunction "7_7") (pintype "passive"))
      (node (ref "U8") (pin "10") (pinfunction "10_10") (pintype "bidirectional"))
    )
    (net (code "53") (name "MEM1_SCK") (class "Default")
      (node (ref "JP25") (pin "5") (pinfunction "5_5") (pintype "passive"))
      (node (ref "JP26") (pin "5") (pinfunction "5_5") (pintype "passive"))
      (node (ref "JP40") (pin "23") (pinfunction "23_23") (pintype "passive"))
      (node (ref "U8") (pin "18") (pinfunction "18_18") (pintype "bidirectional"))
    )
    (net (code "54") (name "MEM1_VCC1") (class "Default")
      (node (ref "JP25") (pin "1") (pinfunction "1_1") (pintype "passive"))
      (node (ref "JP31") (pin "2") (pinfunction "2_2") (pintype "passive"))
    )
    (net (code "55") (name "MEM1_VCC2") (class "Default")
      (node (ref "JP26") (pin "1") (pinfunction "1_1") (pintype "passive"))
      (node (ref "JP32") (pin "2") (pinfunction "2_2") (pintype "passive"))
    )
    (net (code "56") (name "MEM1_~{HOLD}") (class "Default")
      (node (ref "JP25") (pin "3") (pinfunction "3_3") (pintype "passive"))
      (node (ref "JP26") (pin "3") (pinfunction "3_3") (pintype "passive"))
      (node (ref "JP40") (pin "13") (pinfunction "13_13") (pintype "passive"))
      (node (ref "U8") (pin "13") (pinfunction "13_13") (pintype "bidirectional"))
    )
    (net (code "57") (name "MEM1_~{WP}") (class "Default")
      (node (ref "JP23") (pin "5") (pinfunction "5_5") (pintype "passive"))
      (node (ref "JP24") (pin "5") (pinfunction "5_5") (pintype "passive"))
      (node (ref "JP40") (pin "11") (pinfunction "11_11") (pintype "passive"))
      (node (ref "U8") (pin "12") (pinfunction "12_12") (pintype "bidirectional"))
    )
    (net (code "58") (name "MEM2_CIPO") (class "Default")
      (node (ref "JP27") (pin "3") (pinfunction "3_3") (pintype "passive"))
      (node (ref "JP28") (pin "3") (pinfunction "3_3") (pintype "passive"))
      (node (ref "JP41") (pin "7") (pinfunction "7_7") (pintype "passive"))
      (node (ref "U8") (pin "47") (pinfunction "47_47") (pintype "bidirectional"))
    )
    (net (code "59") (name "MEM2_COPI") (class "Default")
      (node (ref "JP29") (pin "7") (pinfunction "7_7") (pintype "passive"))
      (node (ref "JP30") (pin "7") (pinfunction "7_7") (pintype "passive"))
      (node (ref "JP41") (pin "11") (pinfunction "11_11") (pintype "passive"))
      (node (ref "U8") (pin "2") (pinfunction "2_2") (pintype "bidirectional"))
    )
    (net (code "60") (name "MEM2_PS1") (class "Default")
      (node (ref "JP27") (pin "1") (pinfunction "1_1") (pintype "passive"))
      (node (ref "JP41") (pin "3") (pinfunction "3_3") (pintype "passive"))
      (node (ref "U8") (pin "45") (pinfunction "45_45") (pintype "bidirectional"))
    )
    (net (code "61") (name "MEM2_PS2") (class "Default")
      (node (ref "JP28") (pin "1") (pinfunction "1_1") (pintype "passive"))
      (node (ref "JP41") (pin "5") (pinfunction "5_5") (pintype "passive"))
      (node (ref "U8") (pin "46") (pinfunction "46_46") (pintype "bidirectional"))
    )
    (net (code "62") (name "MEM2_SCK") (class "Default")
      (node (ref "JP29") (pin "5") (pinfunction "5_5") (pintype "passive"))
      (node (ref "JP30") (pin "5") (pinfunction "5_5") (pintype "passive"))
      (node (ref "JP41") (pin "13") (pinfunction "13_13") (pintype "passive"))
      (node (ref "U8") (pin "3") (pinfunction "3_3") (pintype "bidirectional"))
    )
    (net (code "63") (name "MEM2_VCC1") (class "Default")
      (node (ref "JP29") (pin "1") (pinfunction "1_1") (pintype "passive"))
      (node (ref "JP33") (pin "2") (pinfunction "2_2") (pintype "passive"))
      (node (ref "JP34") (pin "2") (pinfunction "2_2") (pintype "passive"))
    )
    (net (code "64") (name "MEM2_VCC2") (class "Default")
      (node (ref "JP30") (pin "1") (pinfunction "1_1") (pintype "passive"))
      (node (ref "JP35") (pin "2") (pinfunction "2_2") (pintype "passive"))
      (node (ref "JP36") (pin "2") (pinfunction "2_2") (pintype "passive"))
    )
    (net (code "65") (name "MEM2_~{WP}") (class "Default")
      (node (ref "JP27") (pin "5") (pinfunction "5_5") (pintype "passive"))
      (node (ref "JP28") (pin "5") (pinfunction "5_5") (pintype "passive"))
      (node (ref "JP41") (pin "9") (pinfunction "9_9") (pintype "passive"))
      (node (ref "U8") (pin "48") (pinfunction "48_48") (pintype "bidirectional"))
    )
    (net (code "66") (name "MIC1_VCC") (class "Default")
      (node (ref "C50") (pin "2") (pinfunction "P$2_2") (pintype "bidirectional"))
      (node (ref "C51") (pin "2") (pinfunction "P$2_2") (pintype "bidirectional"))
      (node (ref "JP37") (pin "2") (pinfunction "2_2") (pintype "passive"))
      (node (ref "U12") (pin "P$5") (pinfunction "VDD_P$5") (pintype "bidirectional"))
    )
    (net (code "67") (name "MIC2_VCC") (class "Default")
      (node (ref "C52") (pin "2") (pinfunction "P$2_2") (pintype "bidirectional"))
      (node (ref "C53") (pin "2") (pinfunction "P$2_2") (pintype "bidirectional"))
      (node (ref "JP38") (pin "2") (pinfunction "2_2") (pintype "passive"))
      (node (ref "U13") (pin "P$2") (pinfunction "SEL_P$2") (pintype "bidirectional"))
      (node (ref "U13") (pin "P$5") (pinfunction "VDD_P$5") (pintype "bidirectional"))
    )
    (net (code "68") (name "Net-(C4-P$2)") (class "Default")
      (node (ref "C4") (pin "2") (pinfunction "P$2_2") (pintype "bidirectional"))
      (node (ref "U5") (pin "37") (pinfunction "VCCA_37") (pintype "power_in"))
    )
    (net (code "69") (name "Net-(C5-P$2)") (class "Default")
      (node (ref "C5") (pin "2") (pinfunction "P$2_2") (pintype "bidirectional"))
      (node (ref "U5") (pin "38") (pinfunction "VCCCORE_38") (pintype "power_in"))
    )
    (net (code "70") (name "Net-(C17-P$2)") (class "Default")
      (node (ref "C17") (pin "2") (pinfunction "P$2_2") (pintype "bidirectional"))
      (node (ref "FB1") (pin "2") (pinfunction "P$2_2") (pintype "bidirectional"))
      (node (ref "U5") (pin "8") (pinfunction "VPLL_8") (pintype "power_in"))
    )
    (net (code "71") (name "Net-(C18-P$2)") (class "Default")
      (node (ref "C18") (pin "2") (pinfunction "P$2_2") (pintype "bidirectional"))
      (node (ref "FB2") (pin "2") (pinfunction "P$2_2") (pintype "bidirectional"))
      (node (ref "U5") (pin "3") (pinfunction "VPHY_3") (pintype "power_in"))
    )
    (net (code "72") (name "Net-(C21-P$2)") (class "Default")
      (node (ref "C21") (pin "2") (pinfunction "P$2_2") (pintype "bidirectional"))
      (node (ref "R10") (pin "2") (pinfunction "P$2_2") (pintype "bidirectional"))
      (node (ref "U5") (pin "34") (pinfunction "~{RESET}_34") (pintype "input"))
    )
    (net (code "73") (name "Net-(C32-P$2)") (class "Default")
      (node (ref "C32") (pin "2") (pinfunction "P$2_2") (pintype "bidirectional"))
      (node (ref "C33") (pin "1") (pinfunction "1_1") (pintype "passive"))
      (node (ref "R25") (pin "2") (pinfunction "P$2_2") (pintype "bidirectional"))
      (node (ref "U8") (pin "29") (pinfunction "29_29") (pintype "bidirectional"))
    )
    (net (code "74") (name "Net-(JP39-Pad1)") (class "Default")
      (node (ref "JP39") (pin "1") (pinfunction "1_1") (pintype "passive"))
      (node (ref "SJ1") (pin "2") (pinfunction "2_2") (pintype "passive"))
    )
    (net (code "75") (name "Net-(JP39-Pad3)") (class "Default")
      (node (ref "JP39") (pin "3") (pinfunction "3_3") (pintype "passive"))
      (node (ref "SJ2") (pin "2") (pinfunction "2_2") (pintype "passive"))
    )
    (net (code "76") (name "Net-(JP39-Pad5)") (class "Default")
      (node (ref "JP39") (pin "5") (pinfunction "5_5") (pintype "passive"))
      (node (ref "SJ3") (pin "2") (pinfunction "2_2") (pintype "passive"))
    )
    (net (code "77") (name "Net-(JP39-Pad7)") (class "Default")
      (node (ref "JP39") (pin "7") (pinfunction "7_7") (pintype "passive"))
      (node (ref "SJ4") (pin "2") (pinfunction "2_2") (pintype "passive"))
    )
    (net (code "78") (name "Net-(JP39-Pad9)") (class "Default")
      (node (ref "JP39") (pin "9") (pinfunction "9_9") (pintype "passive"))
      (node (ref "SJ5") (pin "2") (pinfunction "2_2") (pintype "passive"))
    )
    (net (code "79") (name "Net-(JP39-Pad11)") (class "Default")
      (node (ref "JP39") (pin "11") (pinfunction "11_11") (pintype "passive"))
      (node (ref "SJ6") (pin "2") (pinfunction "2_2") (pintype "passive"))
    )
    (net (code "80") (name "Net-(JP39-Pad13)") (class "Default")
      (node (ref "JP39") (pin "13") (pinfunction "13_13") (pintype "passive"))
      (node (ref "SJ7") (pin "2") (pinfunction "2_2") (pintype "passive"))
    )
    (net (code "81") (name "Net-(JP39-Pad15)") (class "Default")
      (node (ref "JP39") (pin "15") (pinfunction "15_15") (pintype "passive"))
      (node (ref "SJ8") (pin "2") (pinfunction "2_2") (pintype "passive"))
    )
    (net (code "82") (name "Net-(JP39-Pad17)") (class "Default")
      (node (ref "JP39") (pin "17") (pinfunction "17_17") (pintype "passive"))
      (node (ref "SJ9") (pin "2") (pinfunction "2_2") (pintype "passive"))
    )
    (net (code "83") (name "Net-(JP39-Pad19)") (class "Default")
      (node (ref "JP39") (pin "19") (pinfunction "19_19") (pintype "passive"))
      (node (ref "SJ10") (pin "2") (pinfunction "2_2") (pintype "passive"))
    )
    (net (code "84") (name "Net-(JP39-Pad21)") (class "Default")
      (node (ref "JP39") (pin "21") (pinfunction "21_21") (pintype "passive"))
      (node (ref "SJ11") (pin "2") (pinfunction "2_2") (pintype "passive"))
    )
    (net (code "85") (name "Net-(JP39-Pad23)") (class "Default")
      (node (ref "JP39") (pin "23") (pinfunction "23_23") (pintype "passive"))
      (node (ref "SJ12") (pin "2") (pinfunction "2_2") (pintype "passive"))
    )
    (net (code "86") (name "Net-(JP39-Pad25)") (class "Default")
      (node (ref "JP39") (pin "25") (pinfunction "25_25") (pintype "passive"))
      (node (ref "SJ13") (pin "2") (pinfunction "2_2") (pintype "passive"))
    )
    (net (code "87") (name "Net-(JP39-Pad27)") (class "Default")
      (node (ref "JP39") (pin "27") (pinfunction "27_27") (pintype "passive"))
      (node (ref "SJ14") (pin "2") (pinfunction "2_2") (pintype "passive"))
    )
    (net (code "88") (name "Net-(JP39-Pad29)") (class "Default")
      (node (ref "JP39") (pin "29") (pinfunction "29_29") (pintype "passive"))
      (node (ref "SJ15") (pin "2") (pinfunction "2_2") (pintype "passive"))
    )
    (net (code "89") (name "Net-(JP39-Pad31)") (class "Default")
      (node (ref "JP39") (pin "31") (pinfunction "31_31") (pintype "passive"))
      (node (ref "SJ16") (pin "2") (pinfunction "2_2") (pintype "passive"))
    )
    (net (code "90") (name "Net-(JP39-Pad33)") (class "Default")
      (node (ref "JP39") (pin "33") (pinfunction "33_33") (pintype "passive"))
      (node (ref "SJ17") (pin "2") (pinfunction "2_2") (pintype "passive"))
    )
    (net (code "91") (name "Net-(R1-P$2)") (class "Default")
      (node (ref "R1") (pin "2") (pinfunction "P$2_2") (pintype "bidirectional"))
      (node (ref "R2") (pin "1") (pinfunction "P$1_1") (pintype "bidirectional"))
      (node (ref "U1") (pin "4") (pinfunction "ADJ_4") (pintype "bidirectional"))
    )
    (net (code "92") (name "Net-(R3-P$2)") (class "Default")
      (node (ref "R3") (pin "2") (pinfunction "P$2_2") (pintype "bidirectional"))
      (node (ref "R4") (pin "1") (pinfunction "P$1_1") (pintype "bidirectional"))
      (node (ref "U3") (pin "4") (pinfunction "ADJ_4") (pintype "bidirectional"))
    )
    (net (code "93") (name "Net-(R5-P$2)") (class "Default")
      (node (ref "R5") (pin "2") (pinfunction "P$2_2") (pintype "bidirectional"))
      (node (ref "R6") (pin "1") (pinfunction "P$1_1") (pintype "bidirectional"))
      (node (ref "U4") (pin "4") (pinfunction "ADJ_4") (pintype "bidirectional"))
    )
    (net (code "94") (name "Net-(R7-P$2)") (class "Default")
      (node (ref "R7") (pin "2") (pinfunction "P$2_2") (pintype "bidirectional"))
      (node (ref "U2") (pin "P$1") (pinfunction "STBY_P$1") (pintype "bidirectional"))
    )
    (net (code "95") (name "Net-(R8-P$2)") (class "Default")
      (node (ref "R8") (pin "2") (pinfunction "P$2_2") (pintype "bidirectional"))
      (node (ref "U5") (pin "5") (pinfunction "REF_5") (pintype "input"))
    )
    (net (code "96") (name "Net-(R9-P$2)") (class "Default")
      (node (ref "R9") (pin "2") (pinfunction "P$2_2") (pintype "bidirectional"))
      (node (ref "U5") (pin "43") (pinfunction "EEDATA_43") (pintype "bidirectional"))
      (node (ref "U6") (pin "3") (pinfunction "DI_3") (pintype "input"))
    )
    (net (code "97") (name "Net-(R11-P$2)") (class "Default")
      (node (ref "R11") (pin "2") (pinfunction "P$2_2") (pintype "bidirectional"))
      (node (ref "R9") (pin "1") (pinfunction "P$1_1") (pintype "bidirectional"))
      (node (ref "U6") (pin "1") (pinfunction "DO_1") (pintype "tri_state"))
    )
    (net (code "98") (name "Net-(R12-P$2)") (class "Default")
      (node (ref "R12") (pin "2") (pinfunction "P$2_2") (pintype "bidirectional"))
      (node (ref "U5") (pin "44") (pinfunction "EECLK_44") (pintype "output"))
      (node (ref "U6") (pin "4") (pinfunction "CLK_4") (pintype "input"))
    )
    (net (code "99") (name "Net-(R13-P$2)") (class "Default")
      (node (ref "R13") (pin "2") (pinfunction "P$2_2") (pintype "bidirectional"))
      (node (ref "U5") (pin "45") (pinfunction "EECS_45") (pintype "bidirectional"))
      (node (ref "U6") (pin "5") (pinfunction "CS_5") (pintype "input"))
    )
    (net (code "100") (name "Net-(R14-P$1)") (class "Default")
      (node (ref "R14") (pin "1") (pinfunction "P$1_1") (pintype "bidirectional"))
      (node (ref "U5") (pin "32") (pinfunction "ACBUS8_32") (pintype "bidirectional"))
    )
    (net (code "101") (name "Net-(R14-P$2)") (class "Default")
      (node (ref "LED1") (pin "C") (pinfunction "C_C") (pintype "passive"))
      (node (ref "R14") (pin "2") (pinfunction "P$2_2") (pintype "bidirectional"))
    )
    (net (code "102") (name "Net-(R15-P$1)") (class "Default")
      (node (ref "R15") (pin "1") (pinfunction "P$1_1") (pintype "bidirectional"))
      (node (ref "U5") (pin "33") (pinfunction "ACBUS9_33") (pintype "bidirectional"))
    )
    (net (code "103") (name "Net-(R15-P$2)") (class "Default")
      (node (ref "LED2") (pin "C") (pinfunction "C_C") (pintype "passive"))
      (node (ref "R15") (pin "2") (pinfunction "P$2_2") (pintype "bidirectional"))
    )
    (net (code "104") (name "Net-(R16-P$2)") (class "Default")
      (node (ref "R16") (pin "2") (pinfunction "P$2_2") (pintype "bidirectional"))
      (node (ref "R17") (pin "1") (pinfunction "P$1_1") (pintype "bidirectional"))
      (node (ref "U5") (pin "31") (pinfunction "ACBUS7_31") (pintype "bidirectional"))
    )
    (net (code "105") (name "Net-(R20-P$2)") (class "Default")
      (node (ref "R20") (pin "2") (pinfunction "P$2_2") (pintype "bidirectional"))
      (node (ref "U7") (pin "3") (pinfunction "W#/DQ2_3") (pintype "bidirectional"))
    )
    (net (code "106") (name "Net-(R21-P$2)") (class "Default")
      (node (ref "R21") (pin "2") (pinfunction "P$2_2") (pintype "bidirectional"))
      (node (ref "U7") (pin "7") (pinfunction "DQ3/HOLD#_7") (pintype "bidirectional"))
    )
    (net (code "107") (name "Net-(R27-P$2)") (class "Default")
      (node (ref "LED3") (pin "A") (pinfunction "A_A") (pintype "passive"))
      (node (ref "R27") (pin "2") (pinfunction "P$2_2") (pintype "bidirectional"))
    )
    (net (code "108") (name "Net-(R30-P$2)") (class "Default")
      (node (ref "R30") (pin "2") (pinfunction "P$2_2") (pintype "bidirectional"))
      (node (ref "R33") (pin "1") (pinfunction "P$1_1") (pintype "bidirectional"))
      (node (ref "U10") (pin "4") (pinfunction "ADJ_4") (pintype "bidirectional"))
    )
    (net (code "109") (name "Net-(R31-P$2)") (class "Default")
      (node (ref "JP21") (pin "1") (pinfunction "1_1") (pintype "passive"))
      (node (ref "R31") (pin "2") (pinfunction "P$2_2") (pintype "bidirectional"))
      (node (ref "U11") (pin "P$1") (pinfunction "STBY_P$1") (pintype "bidirectional"))
    )
    (net (code "110") (name "Net-(R36-P$2)") (class "Default")
      (node (ref "LED4") (pin "A") (pinfunction "A_A") (pintype "passive"))
      (node (ref "R36") (pin "2") (pinfunction "P$2_2") (pintype "bidirectional"))
    )
    (net (code "111") (name "Net-(R37-P$2)") (class "Default")
      (node (ref "LED5") (pin "A") (pinfunction "A_A") (pintype "passive"))
      (node (ref "R37") (pin "2") (pinfunction "P$2_2") (pintype "bidirectional"))
    )
    (net (code "112") (name "Net-(R38-P$2)") (class "Default")
      (node (ref "LED6") (pin "A") (pinfunction "A_A") (pintype "passive"))
      (node (ref "R38") (pin "2") (pinfunction "P$2_2") (pintype "bidirectional"))
    )
    (net (code "113") (name "Net-(U9-IN+1)") (class "Default")
      (node (ref "JP1") (pin "2") (pinfunction "2_2") (pintype "passive"))
      (node (ref "R22") (pin "1") (pinfunction "1_1") (pintype "passive"))
      (node (ref "U9") (pin "3") (pinfunction "IN+1_3") (pintype "bidirectional"))
    )
    (net (code "114") (name "Net-(U9-IN+2)") (class "Default")
      (node (ref "JP2") (pin "2") (pinfunction "2_2") (pintype "passive"))
      (node (ref "R23") (pin "1") (pinfunction "1_1") (pintype "passive"))
      (node (ref "U9") (pin "5") (pinfunction "IN+2_5") (pintype "bidirectional"))
    )
    (net (code "115") (name "Net-(U9-IN+3)") (class "Default")
      (node (ref "JP3") (pin "2") (pinfunction "2_2") (pintype "passive"))
      (node (ref "R24") (pin "1") (pinfunction "1_1") (pintype "passive"))
      (node (ref "U9") (pin "10") (pinfunction "IN+3_10") (pintype "bidirectional"))
    )
    (net (code "116") (name "Net-(U9-IN+4)") (class "Default")
      (node (ref "JP18") (pin "2") (pinfunction "2_2") (pintype "passive"))
      (node (ref "R32") (pin "1") (pinfunction "1_1") (pintype "passive"))
      (node (ref "U9") (pin "12") (pinfunction "IN+4_12") (pintype "bidirectional"))
    )
    (net (code "117") (name "Net-(U9-OUT1)") (class "Default")
      (node (ref "JP10") (pin "1") (pinfunction "1_1") (pintype "passive"))
      (node (ref "U9") (pin "1") (pinfunction "OUT1_1") (pintype "bidirectional"))
    )
    (net (code "118") (name "Net-(U9-OUT2)") (class "Default")
      (node (ref "JP11") (pin "1") (pinfunction "1_1") (pintype "passive"))
      (node (ref "U9") (pin "7") (pinfunction "OUT2_7") (pintype "bidirectional"))
    )
    (net (code "119") (name "Net-(U9-OUT3)") (class "Default")
      (node (ref "JP12") (pin "1") (pinfunction "1_1") (pintype "passive"))
      (node (ref "U9") (pin "8") (pinfunction "OUT3_8") (pintype "bidirectional"))
    )
    (net (code "120") (name "Net-(U9-OUT4)") (class "Default")
      (node (ref "JP15") (pin "1") (pinfunction "1_1") (pintype "passive"))
      (node (ref "U9") (pin "14") (pinfunction "OUT4_14") (pintype "bidirectional"))
    )
    (net (code "121") (name "QWIIC_+3V3") (class "Default")
      (node (ref "J3") (pin "P$2") (pinfunction "P$2_P$2") (pintype "bidirectional"))
      (node (ref "JP22") (pin "2") (pinfunction "2_2") (pintype "passive"))
      (node (ref "R34") (pin "1") (pinfunction "P$1_1") (pintype "bidirectional"))
      (node (ref "R35") (pin "1") (pinfunction "P$1_1") (pintype "bidirectional"))
    )
    (net (code "122") (name "QWIIC_SCL") (class "Default")
      (node (ref "J3") (pin "P$4") (pinfunction "P$4_P$4") (pintype "bidirectional"))
      (node (ref "JP40") (pin "3") (pinfunction "3_3") (pintype "passive"))
      (node (ref "R35") (pin "2") (pinfunction "P$2_2") (pintype "bidirectional"))
      (node (ref "U8") (pin "7") (pinfunction "7_7") (pintype "bidirectional"))
    )
    (net (code "123") (name "QWIIC_SDA") (class "Default")
      (node (ref "J3") (pin "P$3") (pinfunction "P$3_P$3") (pintype "bidirectional"))
      (node (ref "JP40") (pin "1") (pinfunction "1_1") (pintype "passive"))
      (node (ref "R34") (pin "2") (pinfunction "P$2_2") (pintype "bidirectional"))
      (node (ref "U8") (pin "6") (pinfunction "6_6") (pintype "bidirectional"))
    )
    (net (code "124") (name "VUSB") (class "Default")
      (node (ref "C1") (pin "2") (pinfunction "P$2_2") (pintype "bidirectional"))
      (node (ref "C10") (pin "2") (pinfunction "P$2_2") (pintype "bidirectional"))
      (node (ref "C12") (pin "1") (pinfunction "1_1") (pintype "passive"))
      (node (ref "C2") (pin "2") (pinfunction "P$2_2") (pintype "bidirectional"))
      (node (ref "C45") (pin "2") (pinfunction "P$2_2") (pintype "bidirectional"))
      (node (ref "C6") (pin "2") (pinfunction "P$2_2") (pintype "bidirectional"))
      (node (ref "C8") (pin "2") (pinfunction "P$2_2") (pintype "bidirectional"))
      (node (ref "J2") (pin "1") (pinfunction "1_1") (pintype "passive"))
      (node (ref "R16") (pin "1") (pinfunction "P$1_1") (pintype "bidirectional"))
      (node (ref "U1") (pin "1") (pinfunction "VIN_1") (pintype "bidirectional"))
      (node (ref "U1") (pin "3") (pinfunction "EN_3") (pintype "bidirectional"))
      (node (ref "U10") (pin "1") (pinfunction "VIN_1") (pintype "bidirectional"))
      (node (ref "U10") (pin "3") (pinfunction "EN_3") (pintype "bidirectional"))
      (node (ref "U3") (pin "1") (pinfunction "VIN_1") (pintype "bidirectional"))
      (node (ref "U3") (pin "3") (pinfunction "EN_3") (pintype "bidirectional"))
      (node (ref "U4") (pin "1") (pinfunction "VIN_1") (pintype "bidirectional"))
      (node (ref "U4") (pin "3") (pinfunction "EN_3") (pintype "bidirectional"))
      (node (ref "U5") (pin "40") (pinfunction "VREGIN_40") (pintype "power_in"))
    )
    (net (code "125") (name "unconnected-(J1-PadP$1)") (class "Default")
      (node (ref "J1") (pin "P$1") (pinfunction "P$1_P$1") (pintype "bidirectional"))
    )
    (net (code "126") (name "unconnected-(J1-PadP$23)") (class "Default")
      (node (ref "J1") (pin "P$23") (pinfunction "P$23_P$23") (pintype "bidirectional"))
    )
    (net (code "127") (name "unconnected-(J1-PadP$24)") (class "Default")
      (node (ref "J1") (pin "P$24") (pinfunction "P$24_P$24") (pintype "bidirectional"))
    )
    (net (code "128") (name "unconnected-(J2-Pad4)") (class "Default")
      (node (ref "J2") (pin "4") (pinfunction "4_4") (pintype "passive"))
    )
    (net (code "129") (name "unconnected-(JP29-Pad3)") (class "Default")
      (node (ref "JP29") (pin "3") (pinfunction "3_3") (pintype "passive"))
    )
    (net (code "130") (name "unconnected-(JP30-Pad3)") (class "Default")
      (node (ref "JP30") (pin "3") (pinfunction "3_3") (pintype "passive"))
    )
    (net (code "131") (name "unconnected-(U5-ACBUS0{slash}TXDEN-Pad21)") (class "Default")
      (node (ref "U5") (pin "21") (pinfunction "ACBUS0/TXDEN_21") (pintype "bidirectional"))
    )
    (net (code "132") (name "unconnected-(U5-ACBUS1-Pad25)") (class "Default")
      (node (ref "U5") (pin "25") (pinfunction "ACBUS1_25") (pintype "bidirectional"))
    )
    (net (code "133") (name "unconnected-(U5-ACBUS2-Pad26)") (class "Default")
      (node (ref "U5") (pin "26") (pinfunction "ACBUS2_26") (pintype "bidirectional"))
    )
    (net (code "134") (name "unconnected-(U5-ACBUS3{slash}RXLED#-Pad27)") (class "Default")
      (node (ref "U5") (pin "27") (pinfunction "ACBUS3/RXLED#_27") (pintype "bidirectional"))
    )
    (net (code "135") (name "unconnected-(U5-ACBUS4{slash}TXLED#-Pad28)") (class "Default")
      (node (ref "U5") (pin "28") (pinfunction "ACBUS4/TXLED#_28") (pintype "bidirectional"))
    )
    (net (code "136") (name "unconnected-(U5-ACBUS5-Pad29)") (class "Default")
      (node (ref "U5") (pin "29") (pinfunction "ACBUS5_29") (pintype "bidirectional"))
    )
    (net (code "137") (name "unconnected-(U5-ACBUS6-Pad30)") (class "Default")
      (node (ref "U5") (pin "30") (pinfunction "ACBUS6_30") (pintype "bidirectional"))
    )
    (net (code "138") (name "unconnected-(U5-ADBUS3{slash}CTS#-Pad16)") (class "Default")
      (node (ref "U5") (pin "16") (pinfunction "ADBUS3/CTS#_16") (pintype "input"))
    )
    (net (code "139") (name "unconnected-(U5-ADBUS5{slash}DSR#-Pad18)") (class "Default")
      (node (ref "U5") (pin "18") (pinfunction "ADBUS5/DSR#_18") (pintype "input"))
    )
    (net (code "140") (name "unconnected-(U5-ADBUS6{slash}DCD#-Pad19)") (class "Default")
      (node (ref "U5") (pin "19") (pinfunction "ADBUS6/DCD#_19") (pintype "input"))
    )
    (net (code "141") (name "unconnected-(U5-OSCOUT-Pad2)") (class "Default")
      (node (ref "U5") (pin "2") (pinfunction "OSCOUT_2") (pintype "output"))
    )
  )
)
